# BlinkBoard_micro_v1.net
KiCad netlist of a schematic drawn in Altium Designer
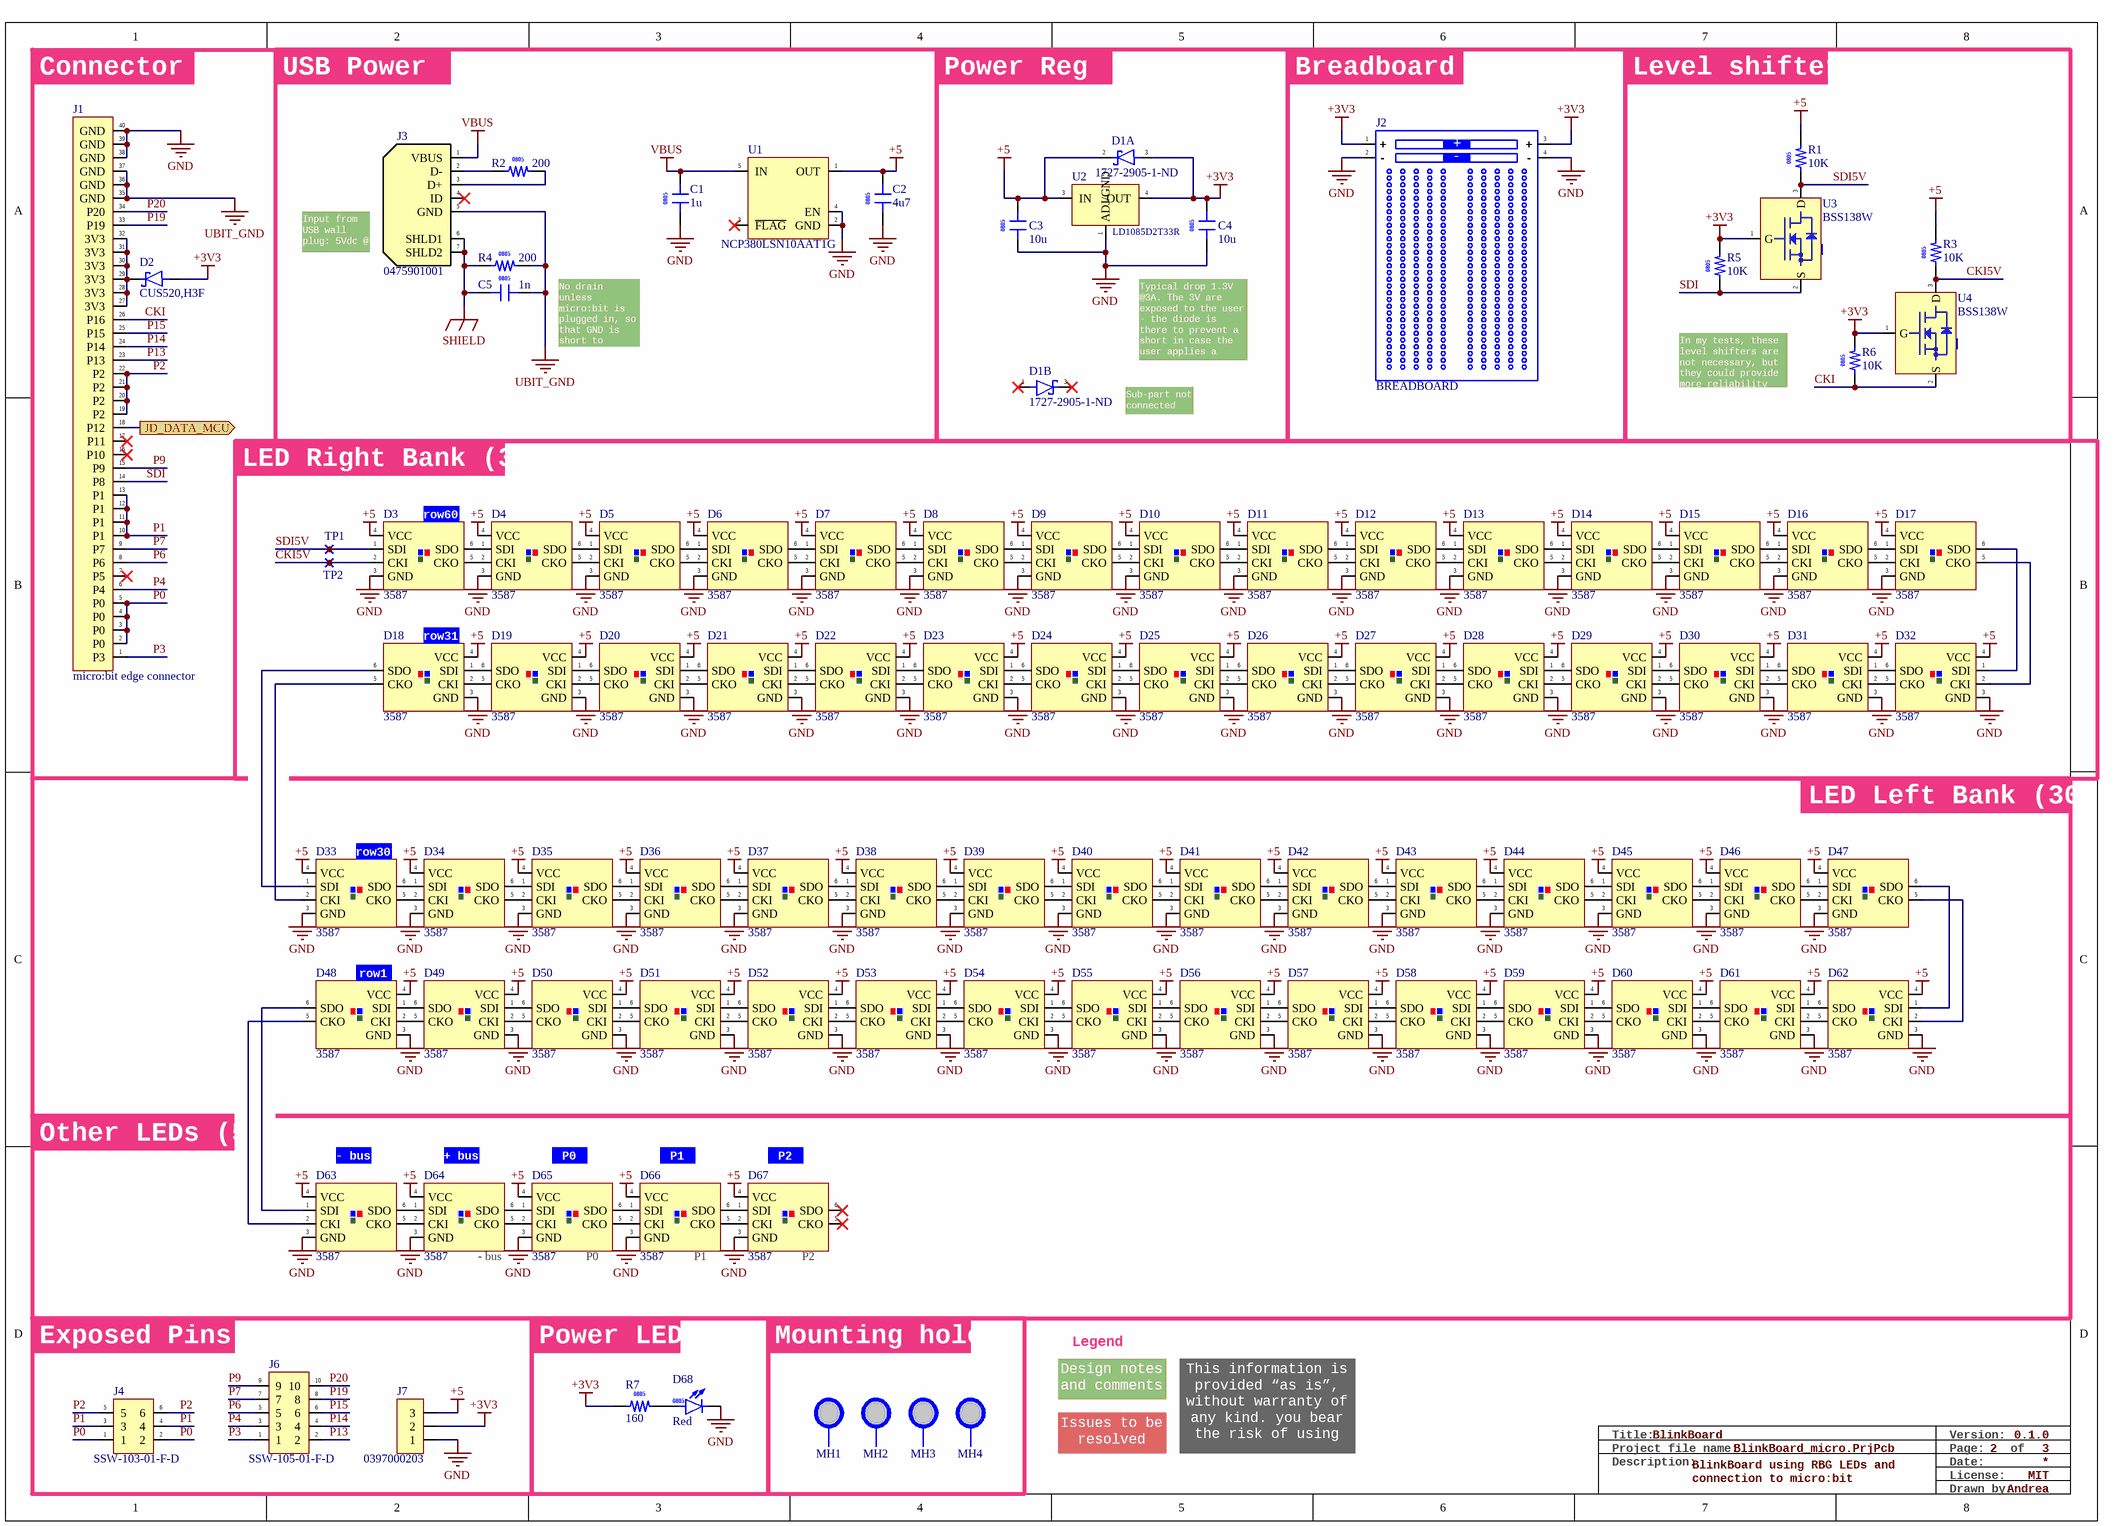
[diagram p0: BlinkBoard_micro_v1.SchDoc]

(export (version "E")
  (design (tool "Eeschema 10.0.6"))
  (components
    (comp (ref "C1")
      (value "1u")
      (footprint "C0805")
      (description "Surface Mount Ceramic Multilayer Capacitor 1uF -20% to 80% Y5V 25V 0805 Paper T/R")
      (fields
        (field (name "MANUFACTURER") "Yageo")
        (field (name "MANUFACTURER PART NUMBER") "CC0805ZRY5V8BB105")
      )
      (libsource (lib "Passives") (part "C0805_1u"))
    )
    (comp (ref "C2")
      (value "4u7")
      (footprint "C0805")
      (description "Multilayer Ceramic Capacitors MLCC - SMD/SMT 4.7uF 6.3V X5R 10%")
      (fields
        (field (name "MANUFACTURER") "Yageo")
        (field (name "MANUFACTURER PART NUMBER") "CC0805KRX5R5BB475")
      )
      (libsource (lib "Passives") (part "C0805_4u7"))
    )
    (comp (ref "C3")
      (value "10u")
      (footprint "C0805")
      (description "Cap Ceramic 10uF 10Vdc X5R 10% SMD 0805 85°C Paper T/R")
      (fields
        (field (name "MANUFACTURER") "Yageo")
        (field (name "MANUFACTURER PART NUMBER") "CC0805KPX5R6BB106")
      )
      (libsource (lib "Passives") (part "C0805_10u"))
    )
    (comp (ref "C4")
      (value "10u")
      (footprint "C0805")
      (description "Cap Ceramic 10uF 10Vdc X5R 10% SMD 0805 85°C Paper T/R")
      (fields
        (field (name "MANUFACTURER") "Yageo")
        (field (name "MANUFACTURER PART NUMBER") "CC0805KPX5R6BB106")
      )
      (libsource (lib "Passives") (part "C0805_10u"))
    )
    (comp (ref "C5")
      (value "1n")
      (footprint "C0805")
      (description "Surface Mount Ceramic Multilayer Capacitor 0.001uF 10% X7R 50V 0805 Paper T/R")
      (fields
        (field (name "MANUFACTURER") "Yageo")
        (field (name "MANUFACTURER PART NUMBER") "CC0805KRX7R9BB102")
      )
      (libsource (lib "Passives") (part "C0805_1n"))
    )
    (comp (ref "D1")
      (value "1727-2905-1-ND")
      (footprint "SOT323")
      (description "Rectifier Diode Schottky 0.2A 5ns Automotive 3-Pin SC-70 T/R")
      (fields
        (field (name "MANUFACTURER") "Nexperia")
        (field (name "MANUFACTURER PART NUMBER") "BAT54SW,115")
      )
      (libsource (lib "Diodes") (part "BAT54SW"))
    )
    (comp (ref "D2")
      (value "CUS520,H3F")
      (footprint "FP-USC-MFG")
      (description "Diode Small Signal Schottky Si 0.2A 2-Pin USC T/R")
      (fields (field (name "MANUFACTURER") "Toshiba"))
      (libsource (lib "Diodes") (part "SCHOTTKY_0.2A"))
    )
    (comp (ref "D3")
      (value "3587")
      (footprint "APA102-2020")
      (description "DotStar Micro LEDs (APA102–2020)- Smart SMD RGB LED - 100 pack")
      (fields (field (name "MANUFACTURER") "Adafruit Industries"))
      (libsource (lib "Diodes") (part "DOT_STAR_LED"))
    )
    (comp (ref "D4")
      (value "3587")
      (footprint "APA102-2020")
      (description "DotStar Micro LEDs (APA102–2020)- Smart SMD RGB LED - 100 pack")
      (fields (field (name "MANUFACTURER") "Adafruit Industries"))
      (libsource (lib "Diodes") (part "DOT_STAR_LED"))
    )
    (comp (ref "D5")
      (value "3587")
      (footprint "APA102-2020")
      (description "DotStar Micro LEDs (APA102–2020)- Smart SMD RGB LED - 100 pack")
      (fields (field (name "MANUFACTURER") "Adafruit Industries"))
      (libsource (lib "Diodes") (part "DOT_STAR_LED"))
    )
    (comp (ref "D6")
      (value "3587")
      (footprint "APA102-2020")
      (description "DotStar Micro LEDs (APA102–2020)- Smart SMD RGB LED - 100 pack")
      (fields (field (name "MANUFACTURER") "Adafruit Industries"))
      (libsource (lib "Diodes") (part "DOT_STAR_LED"))
    )
    (comp (ref "D7")
      (value "3587")
      (footprint "APA102-2020")
      (description "DotStar Micro LEDs (APA102–2020)- Smart SMD RGB LED - 100 pack")
      (fields (field (name "MANUFACTURER") "Adafruit Industries"))
      (libsource (lib "Diodes") (part "DOT_STAR_LED"))
    )
    (comp (ref "D8")
      (value "3587")
      (footprint "APA102-2020")
      (description "DotStar Micro LEDs (APA102–2020)- Smart SMD RGB LED - 100 pack")
      (fields (field (name "MANUFACTURER") "Adafruit Industries"))
      (libsource (lib "Diodes") (part "DOT_STAR_LED"))
    )
    (comp (ref "D9")
      (value "3587")
      (footprint "APA102-2020")
      (description "DotStar Micro LEDs (APA102–2020)- Smart SMD RGB LED - 100 pack")
      (fields (field (name "MANUFACTURER") "Adafruit Industries"))
      (libsource (lib "Diodes") (part "DOT_STAR_LED"))
    )
    (comp (ref "D10")
      (value "3587")
      (footprint "APA102-2020")
      (description "DotStar Micro LEDs (APA102–2020)- Smart SMD RGB LED - 100 pack")
      (fields (field (name "MANUFACTURER") "Adafruit Industries"))
      (libsource (lib "Diodes") (part "DOT_STAR_LED"))
    )
    (comp (ref "D11")
      (value "3587")
      (footprint "APA102-2020")
      (description "DotStar Micro LEDs (APA102–2020)- Smart SMD RGB LED - 100 pack")
      (fields (field (name "MANUFACTURER") "Adafruit Industries"))
      (libsource (lib "Diodes") (part "DOT_STAR_LED"))
    )
    (comp (ref "D12")
      (value "3587")
      (footprint "APA102-2020")
      (description "DotStar Micro LEDs (APA102–2020)- Smart SMD RGB LED - 100 pack")
      (fields (field (name "MANUFACTURER") "Adafruit Industries"))
      (libsource (lib "Diodes") (part "DOT_STAR_LED"))
    )
    (comp (ref "D13")
      (value "3587")
      (footprint "APA102-2020")
      (description "DotStar Micro LEDs (APA102–2020)- Smart SMD RGB LED - 100 pack")
      (fields (field (name "MANUFACTURER") "Adafruit Industries"))
      (libsource (lib "Diodes") (part "DOT_STAR_LED"))
    )
    (comp (ref "D14")
      (value "3587")
      (footprint "APA102-2020")
      (description "DotStar Micro LEDs (APA102–2020)- Smart SMD RGB LED - 100 pack")
      (fields (field (name "MANUFACTURER") "Adafruit Industries"))
      (libsource (lib "Diodes") (part "DOT_STAR_LED"))
    )
    (comp (ref "D15")
      (value "3587")
      (footprint "APA102-2020")
      (description "DotStar Micro LEDs (APA102–2020)- Smart SMD RGB LED - 100 pack")
      (fields (field (name "MANUFACTURER") "Adafruit Industries"))
      (libsource (lib "Diodes") (part "DOT_STAR_LED"))
    )
    (comp (ref "D16")
      (value "3587")
      (footprint "APA102-2020")
      (description "DotStar Micro LEDs (APA102–2020)- Smart SMD RGB LED - 100 pack")
      (fields (field (name "MANUFACTURER") "Adafruit Industries"))
      (libsource (lib "Diodes") (part "DOT_STAR_LED"))
    )
    (comp (ref "D17")
      (value "3587")
      (footprint "APA102-2020")
      (description "DotStar Micro LEDs (APA102–2020)- Smart SMD RGB LED - 100 pack")
      (fields (field (name "MANUFACTURER") "Adafruit Industries"))
      (libsource (lib "Diodes") (part "DOT_STAR_LED"))
    )
    (comp (ref "D18")
      (value "3587")
      (footprint "APA102-2020")
      (description "DotStar Micro LEDs (APA102–2020)- Smart SMD RGB LED - 100 pack")
      (fields (field (name "MANUFACTURER") "Adafruit Industries"))
      (libsource (lib "") (part "DOT_STAR_LED_1"))
    )
    (comp (ref "D19")
      (value "3587")
      (footprint "APA102-2020")
      (description "DotStar Micro LEDs (APA102–2020)- Smart SMD RGB LED - 100 pack")
      (fields (field (name "MANUFACTURER") "Adafruit Industries"))
      (libsource (lib "") (part "DOT_STAR_LED_1"))
    )
    (comp (ref "D20")
      (value "3587")
      (footprint "APA102-2020")
      (description "DotStar Micro LEDs (APA102–2020)- Smart SMD RGB LED - 100 pack")
      (fields (field (name "MANUFACTURER") "Adafruit Industries"))
      (libsource (lib "") (part "DOT_STAR_LED_1"))
    )
    (comp (ref "D21")
      (value "3587")
      (footprint "APA102-2020")
      (description "DotStar Micro LEDs (APA102–2020)- Smart SMD RGB LED - 100 pack")
      (fields (field (name "MANUFACTURER") "Adafruit Industries"))
      (libsource (lib "") (part "DOT_STAR_LED_1"))
    )
    (comp (ref "D22")
      (value "3587")
      (footprint "APA102-2020")
      (description "DotStar Micro LEDs (APA102–2020)- Smart SMD RGB LED - 100 pack")
      (fields (field (name "MANUFACTURER") "Adafruit Industries"))
      (libsource (lib "") (part "DOT_STAR_LED_1"))
    )
    (comp (ref "D23")
      (value "3587")
      (footprint "APA102-2020")
      (description "DotStar Micro LEDs (APA102–2020)- Smart SMD RGB LED - 100 pack")
      (fields (field (name "MANUFACTURER") "Adafruit Industries"))
      (libsource (lib "") (part "DOT_STAR_LED_1"))
    )
    (comp (ref "D24")
      (value "3587")
      (footprint "APA102-2020")
      (description "DotStar Micro LEDs (APA102–2020)- Smart SMD RGB LED - 100 pack")
      (fields (field (name "MANUFACTURER") "Adafruit Industries"))
      (libsource (lib "") (part "DOT_STAR_LED_1"))
    )
    (comp (ref "D25")
      (value "3587")
      (footprint "APA102-2020")
      (description "DotStar Micro LEDs (APA102–2020)- Smart SMD RGB LED - 100 pack")
      (fields (field (name "MANUFACTURER") "Adafruit Industries"))
      (libsource (lib "") (part "DOT_STAR_LED_1"))
    )
    (comp (ref "D26")
      (value "3587")
      (footprint "APA102-2020")
      (description "DotStar Micro LEDs (APA102–2020)- Smart SMD RGB LED - 100 pack")
      (fields (field (name "MANUFACTURER") "Adafruit Industries"))
      (libsource (lib "") (part "DOT_STAR_LED_1"))
    )
    (comp (ref "D27")
      (value "3587")
      (footprint "APA102-2020")
      (description "DotStar Micro LEDs (APA102–2020)- Smart SMD RGB LED - 100 pack")
      (fields (field (name "MANUFACTURER") "Adafruit Industries"))
      (libsource (lib "") (part "DOT_STAR_LED_1"))
    )
    (comp (ref "D28")
      (value "3587")
      (footprint "APA102-2020")
      (description "DotStar Micro LEDs (APA102–2020)- Smart SMD RGB LED - 100 pack")
      (fields (field (name "MANUFACTURER") "Adafruit Industries"))
      (libsource (lib "") (part "DOT_STAR_LED_1"))
    )
    (comp (ref "D29")
      (value "3587")
      (footprint "APA102-2020")
      (description "DotStar Micro LEDs (APA102–2020)- Smart SMD RGB LED - 100 pack")
      (fields (field (name "MANUFACTURER") "Adafruit Industries"))
      (libsource (lib "") (part "DOT_STAR_LED_1"))
    )
    (comp (ref "D30")
      (value "3587")
      (footprint "APA102-2020")
      (description "DotStar Micro LEDs (APA102–2020)- Smart SMD RGB LED - 100 pack")
      (fields (field (name "MANUFACTURER") "Adafruit Industries"))
      (libsource (lib "") (part "DOT_STAR_LED_1"))
    )
    (comp (ref "D31")
      (value "3587")
      (footprint "APA102-2020")
      (description "DotStar Micro LEDs (APA102–2020)- Smart SMD RGB LED - 100 pack")
      (fields (field (name "MANUFACTURER") "Adafruit Industries"))
      (libsource (lib "") (part "DOT_STAR_LED_1"))
    )
    (comp (ref "D32")
      (value "3587")
      (footprint "APA102-2020")
      (description "DotStar Micro LEDs (APA102–2020)- Smart SMD RGB LED - 100 pack")
      (fields (field (name "MANUFACTURER") "Adafruit Industries"))
      (libsource (lib "") (part "DOT_STAR_LED_1"))
    )
    (comp (ref "D33")
      (value "3587")
      (footprint "APA102-2020")
      (description "DotStar Micro LEDs (APA102–2020)- Smart SMD RGB LED - 100 pack")
      (fields (field (name "MANUFACTURER") "Adafruit Industries"))
      (libsource (lib "Diodes") (part "DOT_STAR_LED"))
    )
    (comp (ref "D34")
      (value "3587")
      (footprint "APA102-2020")
      (description "DotStar Micro LEDs (APA102–2020)- Smart SMD RGB LED - 100 pack")
      (fields (field (name "MANUFACTURER") "Adafruit Industries"))
      (libsource (lib "Diodes") (part "DOT_STAR_LED"))
    )
    (comp (ref "D35")
      (value "3587")
      (footprint "APA102-2020")
      (description "DotStar Micro LEDs (APA102–2020)- Smart SMD RGB LED - 100 pack")
      (fields (field (name "MANUFACTURER") "Adafruit Industries"))
      (libsource (lib "Diodes") (part "DOT_STAR_LED"))
    )
    (comp (ref "D36")
      (value "3587")
      (footprint "APA102-2020")
      (description "DotStar Micro LEDs (APA102–2020)- Smart SMD RGB LED - 100 pack")
      (fields (field (name "MANUFACTURER") "Adafruit Industries"))
      (libsource (lib "Diodes") (part "DOT_STAR_LED"))
    )
    (comp (ref "D37")
      (value "3587")
      (footprint "APA102-2020")
      (description "DotStar Micro LEDs (APA102–2020)- Smart SMD RGB LED - 100 pack")
      (fields (field (name "MANUFACTURER") "Adafruit Industries"))
      (libsource (lib "Diodes") (part "DOT_STAR_LED"))
    )
    (comp (ref "D38")
      (value "3587")
      (footprint "APA102-2020")
      (description "DotStar Micro LEDs (APA102–2020)- Smart SMD RGB LED - 100 pack")
      (fields (field (name "MANUFACTURER") "Adafruit Industries"))
      (libsource (lib "Diodes") (part "DOT_STAR_LED"))
    )
    (comp (ref "D39")
      (value "3587")
      (footprint "APA102-2020")
      (description "DotStar Micro LEDs (APA102–2020)- Smart SMD RGB LED - 100 pack")
      (fields (field (name "MANUFACTURER") "Adafruit Industries"))
      (libsource (lib "Diodes") (part "DOT_STAR_LED"))
    )
    (comp (ref "D40")
      (value "3587")
      (footprint "APA102-2020")
      (description "DotStar Micro LEDs (APA102–2020)- Smart SMD RGB LED - 100 pack")
      (fields (field (name "MANUFACTURER") "Adafruit Industries"))
      (libsource (lib "Diodes") (part "DOT_STAR_LED"))
    )
    (comp (ref "D41")
      (value "3587")
      (footprint "APA102-2020")
      (description "DotStar Micro LEDs (APA102–2020)- Smart SMD RGB LED - 100 pack")
      (fields (field (name "MANUFACTURER") "Adafruit Industries"))
      (libsource (lib "Diodes") (part "DOT_STAR_LED"))
    )
    (comp (ref "D42")
      (value "3587")
      (footprint "APA102-2020")
      (description "DotStar Micro LEDs (APA102–2020)- Smart SMD RGB LED - 100 pack")
      (fields (field (name "MANUFACTURER") "Adafruit Industries"))
      (libsource (lib "Diodes") (part "DOT_STAR_LED"))
    )
    (comp (ref "D43")
      (value "3587")
      (footprint "APA102-2020")
      (description "DotStar Micro LEDs (APA102–2020)- Smart SMD RGB LED - 100 pack")
      (fields (field (name "MANUFACTURER") "Adafruit Industries"))
      (libsource (lib "Diodes") (part "DOT_STAR_LED"))
    )
    (comp (ref "D44")
      (value "3587")
      (footprint "APA102-2020")
      (description "DotStar Micro LEDs (APA102–2020)- Smart SMD RGB LED - 100 pack")
      (fields (field (name "MANUFACTURER") "Adafruit Industries"))
      (libsource (lib "Diodes") (part "DOT_STAR_LED"))
    )
    (comp (ref "D45")
      (value "3587")
      (footprint "APA102-2020")
      (description "DotStar Micro LEDs (APA102–2020)- Smart SMD RGB LED - 100 pack")
      (fields (field (name "MANUFACTURER") "Adafruit Industries"))
      (libsource (lib "Diodes") (part "DOT_STAR_LED"))
    )
    (comp (ref "D46")
      (value "3587")
      (footprint "APA102-2020")
      (description "DotStar Micro LEDs (APA102–2020)- Smart SMD RGB LED - 100 pack")
      (fields (field (name "MANUFACTURER") "Adafruit Industries"))
      (libsource (lib "Diodes") (part "DOT_STAR_LED"))
    )
    (comp (ref "D47")
      (value "3587")
      (footprint "APA102-2020")
      (description "DotStar Micro LEDs (APA102–2020)- Smart SMD RGB LED - 100 pack")
      (fields (field (name "MANUFACTURER") "Adafruit Industries"))
      (libsource (lib "Diodes") (part "DOT_STAR_LED"))
    )
    (comp (ref "D48")
      (value "3587")
      (footprint "APA102-2020")
      (description "DotStar Micro LEDs (APA102–2020)- Smart SMD RGB LED - 100 pack")
      (fields (field (name "MANUFACTURER") "Adafruit Industries"))
      (libsource (lib "") (part "DOT_STAR_LED_1"))
    )
    (comp (ref "D49")
      (value "3587")
      (footprint "APA102-2020")
      (description "DotStar Micro LEDs (APA102–2020)- Smart SMD RGB LED - 100 pack")
      (fields (field (name "MANUFACTURER") "Adafruit Industries"))
      (libsource (lib "") (part "DOT_STAR_LED_1"))
    )
    (comp (ref "D50")
      (value "3587")
      (footprint "APA102-2020")
      (description "DotStar Micro LEDs (APA102–2020)- Smart SMD RGB LED - 100 pack")
      (fields (field (name "MANUFACTURER") "Adafruit Industries"))
      (libsource (lib "") (part "DOT_STAR_LED_1"))
    )
    (comp (ref "D51")
      (value "3587")
      (footprint "APA102-2020")
      (description "DotStar Micro LEDs (APA102–2020)- Smart SMD RGB LED - 100 pack")
      (fields (field (name "MANUFACTURER") "Adafruit Industries"))
      (libsource (lib "") (part "DOT_STAR_LED_1"))
    )
    (comp (ref "D52")
      (value "3587")
      (footprint "APA102-2020")
      (description "DotStar Micro LEDs (APA102–2020)- Smart SMD RGB LED - 100 pack")
      (fields (field (name "MANUFACTURER") "Adafruit Industries"))
      (libsource (lib "") (part "DOT_STAR_LED_1"))
    )
    (comp (ref "D53")
      (value "3587")
      (footprint "APA102-2020")
      (description "DotStar Micro LEDs (APA102–2020)- Smart SMD RGB LED - 100 pack")
      (fields (field (name "MANUFACTURER") "Adafruit Industries"))
      (libsource (lib "") (part "DOT_STAR_LED_1"))
    )
    (comp (ref "D54")
      (value "3587")
      (footprint "APA102-2020")
      (description "DotStar Micro LEDs (APA102–2020)- Smart SMD RGB LED - 100 pack")
      (fields (field (name "MANUFACTURER") "Adafruit Industries"))
      (libsource (lib "") (part "DOT_STAR_LED_1"))
    )
    (comp (ref "D55")
      (value "3587")
      (footprint "APA102-2020")
      (description "DotStar Micro LEDs (APA102–2020)- Smart SMD RGB LED - 100 pack")
      (fields (field (name "MANUFACTURER") "Adafruit Industries"))
      (libsource (lib "") (part "DOT_STAR_LED_1"))
    )
    (comp (ref "D56")
      (value "3587")
      (footprint "APA102-2020")
      (description "DotStar Micro LEDs (APA102–2020)- Smart SMD RGB LED - 100 pack")
      (fields (field (name "MANUFACTURER") "Adafruit Industries"))
      (libsource (lib "") (part "DOT_STAR_LED_1"))
    )
    (comp (ref "D57")
      (value "3587")
      (footprint "APA102-2020")
      (description "DotStar Micro LEDs (APA102–2020)- Smart SMD RGB LED - 100 pack")
      (fields (field (name "MANUFACTURER") "Adafruit Industries"))
      (libsource (lib "") (part "DOT_STAR_LED_1"))
    )
    (comp (ref "D58")
      (value "3587")
      (footprint "APA102-2020")
      (description "DotStar Micro LEDs (APA102–2020)- Smart SMD RGB LED - 100 pack")
      (fields (field (name "MANUFACTURER") "Adafruit Industries"))
      (libsource (lib "") (part "DOT_STAR_LED_1"))
    )
    (comp (ref "D59")
      (value "3587")
      (footprint "APA102-2020")
      (description "DotStar Micro LEDs (APA102–2020)- Smart SMD RGB LED - 100 pack")
      (fields (field (name "MANUFACTURER") "Adafruit Industries"))
      (libsource (lib "") (part "DOT_STAR_LED_1"))
    )
    (comp (ref "D60")
      (value "3587")
      (footprint "APA102-2020")
      (description "DotStar Micro LEDs (APA102–2020)- Smart SMD RGB LED - 100 pack")
      (fields (field (name "MANUFACTURER") "Adafruit Industries"))
      (libsource (lib "") (part "DOT_STAR_LED_1"))
    )
    (comp (ref "D61")
      (value "3587")
      (footprint "APA102-2020")
      (description "DotStar Micro LEDs (APA102–2020)- Smart SMD RGB LED - 100 pack")
      (fields (field (name "MANUFACTURER") "Adafruit Industries"))
      (libsource (lib "") (part "DOT_STAR_LED_1"))
    )
    (comp (ref "D62")
      (value "3587")
      (footprint "APA102-2020")
      (description "DotStar Micro LEDs (APA102–2020)- Smart SMD RGB LED - 100 pack")
      (fields (field (name "MANUFACTURER") "Adafruit Industries"))
      (libsource (lib "") (part "DOT_STAR_LED_1"))
    )
    (comp (ref "D63")
      (value "3587")
      (footprint "APA102-2020")
      (description "DotStar Micro LEDs (APA102–2020)- Smart SMD RGB LED - 100 pack")
      (fields (field (name "MANUFACTURER") "Adafruit Industries"))
      (libsource (lib "Diodes") (part "DOT_STAR_LED"))
    )
    (comp (ref "D64")
      (value "3587")
      (footprint "APA102-2020")
      (description "DotStar Micro LEDs (APA102–2020)- Smart SMD RGB LED - 100 pack")
      (fields (field (name "MANUFACTURER") "Adafruit Industries"))
      (libsource (lib "Diodes") (part "DOT_STAR_LED"))
    )
    (comp (ref "D65")
      (value "3587")
      (footprint "APA102-2020")
      (description "DotStar Micro LEDs (APA102–2020)- Smart SMD RGB LED - 100 pack")
      (fields (field (name "MANUFACTURER") "Adafruit Industries"))
      (libsource (lib "Diodes") (part "DOT_STAR_LED"))
    )
    (comp (ref "D66")
      (value "3587")
      (footprint "APA102-2020")
      (description "DotStar Micro LEDs (APA102–2020)- Smart SMD RGB LED - 100 pack")
      (fields (field (name "MANUFACTURER") "Adafruit Industries"))
      (libsource (lib "Diodes") (part "DOT_STAR_LED"))
    )
    (comp (ref "D67")
      (value "3587")
      (footprint "APA102-2020")
      (description "DotStar Micro LEDs (APA102–2020)- Smart SMD RGB LED - 100 pack")
      (fields (field (name "MANUFACTURER") "Adafruit Industries"))
      (libsource (lib "Diodes") (part "DOT_STAR_LED"))
    )
    (comp (ref "D68")
      (value "Red")
      (footprint "LED0805")
      (description "SMD LED red 2.4 V 0805, 150080RS75000, Würth Elektronik")
      (fields
        (field (name "MANUFACTURER") "Wurth Electronics")
        (field (name "MANUFACTURER PART NUMBER") "150080RS75000")
      )
      (libsource (lib "Diodes") (part "LED0805"))
    )
    (comp (ref "J1")
      (value "micro:bit edge connector")
      (footprint "EDGE_CONNECTOR_40")
      (description "3887 - SMT Right-Angle Connector for micro:bit")
      (fields
        (field (name "MANUFACTURER") "Adafruit Industries")
        (field (name "MANUFACTURER PART NUMBER") "3887")
      )
      (libsource (lib "Mechanical") (part "EDGE_CONNECTOR_40"))
    )
    (comp (ref "J2")
      (value "BREADBOARD")
      (footprint "BREADBOARD")
      (description "Breadboard with 2 columns of 30 rows + VCC and GND rails")
      (libsource (lib "Mechanical") (part "BREADBOARD_60"))
    )
    (comp (ref "J3")
      (value "0475901001")
      (footprint "USB_MICRO")
      (description "USB - micro AB  Receptacle Connector 5 Position Surface Mount, Right Angle, Horizontal")
      (fields (field (name "MANUFACTURER") "Molex"))
      (libsource (lib "Mechanical") (part "USB_MICRO"))
    )
    (comp (ref "J4")
      (value "SSW-103-01-F-D")
      (footprint "HDR_6_2.54")
      (description "SAMTEC - SSW-103-01-F-D - CONNECTOR, RECEPTACLE, 6 CONTACTS, 2 ROWS, 2.54 MM")
      (fields (field (name "MANUFACTURER") "Samtec"))
      (libsource (lib "Mechanical") (part "HDR_6_2.54"))
    )
    (comp (ref "J6")
      (value "SSW-105-01-F-D")
      (footprint "HDR_10_2.54")
      (description "Conn Socket Strip SKT 10 POS 2.54mm Solder ST Thru-Hole")
      (fields (field (name "MANUFACTURER") "Samtec"))
      (libsource (lib "Mechanical") (part "HDR_10_2.54"))
    )
    (comp (ref "J7")
      (value "0397000203")
      (footprint "TERM_BLOCK_3POS")
      (description "SPRING TERMINAL BLOCK 3CVERT GRE")
      (fields (field (name "MANUFACTURER") "Molex") (field (name "VOLTAGE") "150V"))
      (libsource (lib "Mechanical") (part "TERM_BLOCK_3POS"))
    )
    (comp (ref "MH1")
      (value "MH 3.2mm NP")
      (footprint "MH3.2MM")
      (description "Mounting hole 3.2mm non plated")
      (libsource (lib "Mechanical") (part "MHNP"))
    )
    (comp (ref "MH2")
      (value "MH 3.2mm NP")
      (footprint "MH3.2MM")
      (description "Mounting hole 3.2mm non plated")
      (libsource (lib "Mechanical") (part "MHNP"))
    )
    (comp (ref "MH3")
      (value "MH 3.2mm NP")
      (footprint "MH3.2MM")
      (description "Mounting hole 3.2mm non plated")
      (libsource (lib "Mechanical") (part "MHNP"))
    )
    (comp (ref "MH4")
      (value "MH 3.2mm NP")
      (footprint "MH3.2MM")
      (description "Mounting hole 3.2mm non plated")
      (libsource (lib "Mechanical") (part "MHNP"))
    )
    (comp (ref "R1")
      (value "10K")
      (footprint "R0805")
      (description "Res Thick Film 0805 10K Ohm 5% 1/8W ±100ppm/°C Molded SMD Paper T/R")
      (fields
        (field (name "MANUFACTURER") "Yageo")
        (field (name "MANUFACTURER PART NUMBER") "RC0805JR-0710KL")
      )
      (libsource (lib "Passives") (part "R0805_10K"))
    )
    (comp (ref "R2")
      (value "200")
      (footprint "R0805")
      (description "RES SMD 200 OHM 0.5% 1/8W 0805")
      (fields
        (field (name "MANUFACTURER") "Yageo")
        (field (name "MANUFACTURER PART NUMBER") "RT0805DRE07200RL")
      )
      (libsource (lib "Passives") (part "R0805_200"))
    )
    (comp (ref "R3")
      (value "10K")
      (footprint "R0805")
      (description "Res Thick Film 0805 10K Ohm 5% 1/8W ±100ppm/°C Molded SMD Paper T/R")
      (fields
        (field (name "MANUFACTURER") "Yageo")
        (field (name "MANUFACTURER PART NUMBER") "RC0805JR-0710KL")
      )
      (libsource (lib "Passives") (part "R0805_10K"))
    )
    (comp (ref "R4")
      (value "200")
      (footprint "R0805")
      (description "RES SMD 200 OHM 0.5% 1/8W 0805")
      (fields
        (field (name "MANUFACTURER") "Yageo")
        (field (name "MANUFACTURER PART NUMBER") "RT0805DRE07200RL")
      )
      (libsource (lib "Passives") (part "R0805_200"))
    )
    (comp (ref "R5")
      (value "10K")
      (footprint "R0805")
      (description "Res Thick Film 0805 10K Ohm 5% 1/8W ±100ppm/°C Molded SMD Paper T/R")
      (fields
        (field (name "MANUFACTURER") "Yageo")
        (field (name "MANUFACTURER PART NUMBER") "RC0805JR-0710KL")
      )
      (libsource (lib "Passives") (part "R0805_10K"))
    )
    (comp (ref "R6")
      (value "10K")
      (footprint "R0805")
      (description "Res Thick Film 0805 10K Ohm 5% 1/8W ±100ppm/°C Molded SMD Paper T/R")
      (fields
        (field (name "MANUFACTURER") "Yageo")
        (field (name "MANUFACTURER PART NUMBER") "RC0805JR-0710KL")
      )
      (libsource (lib "Passives") (part "R0805_10K"))
    )
    (comp (ref "R7")
      (value "160")
      (footprint "R0805")
      (description "RES SMD 160 OHM 5% 1/8W 0805")
      (fields
        (field (name "MANUFACTURER") "Yageo")
        (field (name "MANUFACTURER PART NUMBER") "RC0805JR-07160RL")
      )
      (libsource (lib "Passives") (part "R0805_160"))
    )
    (comp (ref "TP1")
      (value "TEST")
      (footprint "TEST POINT")
      (description "Test point")
      (libsource (lib "Mechanical") (part "TEST"))
    )
    (comp (ref "TP2")
      (value "TEST")
      (footprint "TEST POINT")
      (description "Test point")
      (libsource (lib "Mechanical") (part "TEST"))
    )
    (comp (ref "U1")
      (value "NCP380LSN10AAT1G")
      (footprint "TSOP-5")
      (description "REEL / OVER CURRENT PROTECTION")
      (fields (field (name "MANUFACTURER") "ON Semiconductor"))
      (libsource (lib "IC") (part "NCP380"))
    )
    (comp (ref "U2")
      (value "LD1085D2T33R")
      (footprint "D2PAK")
      (description "Fixed LDO Voltage Regulator, 6.3V to 30V, 1.3V Dropout, 3.3Vout, 3Aout, TO-263-3")
      (fields (field (name "MANUFACTURER") "STMicroelectronics"))
      (libsource (lib "IC") (part "LD1085D2T33R"))
    )
    (comp (ref "U3")
      (value "BSS138W")
      (footprint "SOT323")
      (description "MOSFET 50V N-CH Logic Level")
      (fields (field (name "MANUFACTURER") "Fairchild Semiconductor"))
      (libsource (lib "IC") (part "BSS138W"))
    )
    (comp (ref "U4")
      (value "BSS138W")
      (footprint "SOT323")
      (description "MOSFET 50V N-CH Logic Level")
      (fields (field (name "MANUFACTURER") "Fairchild Semiconductor"))
      (libsource (lib "IC") (part "BSS138W"))
    )
  )
  (nets
    (net (code "1") (name "+3V3") (class "Default")
      (node (ref "C4") (pin "2") (pinfunction "2_2") (pintype "passive"))
      (node (ref "D1") (pin "3") (pinfunction "3_3") (pintype "passive"))
      (node (ref "D2") (pin "2") (pinfunction "A_2") (pintype "passive"))
      (node (ref "J2") (pin "1") (pinfunction "+_1") (pintype "passive"))
      (node (ref "J2") (pin "3") (pinfunction "+_3") (pintype "passive"))
      (node (ref "J7") (pin "2") (pinfunction "2_2") (pintype "passive"))
      (node (ref "R5") (pin "2") (pinfunction "2_2") (pintype "passive"))
      (node (ref "R6") (pin "2") (pinfunction "2_2") (pintype "passive"))
      (node (ref "R7") (pin "1") (pinfunction "1_1") (pintype "passive"))
      (node (ref "U2") (pin "4") (pinfunction "OUT_4") (pintype "passive"))
      (node (ref "U3") (pin "1") (pinfunction "G_1") (pintype "passive"))
      (node (ref "U4") (pin "1") (pinfunction "G_1") (pintype "passive"))
    )
    (net (code "2") (name "+5") (class "Default")
      (node (ref "C2") (pin "2") (pinfunction "2_2") (pintype "passive"))
      (node (ref "C3") (pin "2") (pinfunction "2_2") (pintype "passive"))
      (node (ref "D1") (pin "2") (pinfunction "2_2") (pintype "passive"))
      (node (ref "D10") (pin "4") (pinfunction "VCC_4") (pintype "passive"))
      (node (ref "D11") (pin "4") (pinfunction "VCC_4") (pintype "passive"))
      (node (ref "D12") (pin "4") (pinfunction "VCC_4") (pintype "passive"))
      (node (ref "D13") (pin "4") (pinfunction "VCC_4") (pintype "passive"))
      (node (ref "D14") (pin "4") (pinfunction "VCC_4") (pintype "passive"))
      (node (ref "D15") (pin "4") (pinfunction "VCC_4") (pintype "passive"))
      (node (ref "D16") (pin "4") (pinfunction "VCC_4") (pintype "passive"))
      (node (ref "D17") (pin "4") (pinfunction "VCC_4") (pintype "passive"))
      (node (ref "D18") (pin "4") (pinfunction "VCC_4") (pintype "passive"))
      (node (ref "D19") (pin "4") (pinfunction "VCC_4") (pintype "passive"))
      (node (ref "D20") (pin "4") (pinfunction "VCC_4") (pintype "passive"))
      (node (ref "D21") (pin "4") (pinfunction "VCC_4") (pintype "passive"))
      (node (ref "D22") (pin "4") (pinfunction "VCC_4") (pintype "passive"))
      (node (ref "D23") (pin "4") (pinfunction "VCC_4") (pintype "passive"))
      (node (ref "D24") (pin "4") (pinfunction "VCC_4") (pintype "passive"))
      (node (ref "D25") (pin "4") (pinfunction "VCC_4") (pintype "passive"))
      (node (ref "D26") (pin "4") (pinfunction "VCC_4") (pintype "passive"))
      (node (ref "D27") (pin "4") (pinfunction "VCC_4") (pintype "passive"))
      (node (ref "D28") (pin "4") (pinfunction "VCC_4") (pintype "passive"))
      (node (ref "D29") (pin "4") (pinfunction "VCC_4") (pintype "passive"))
      (node (ref "D3") (pin "4") (pinfunction "VCC_4") (pintype "passive"))
      (node (ref "D30") (pin "4") (pinfunction "VCC_4") (pintype "passive"))
      (node (ref "D31") (pin "4") (pinfunction "VCC_4") (pintype "passive"))
      (node (ref "D32") (pin "4") (pinfunction "VCC_4") (pintype "passive"))
      (node (ref "D33") (pin "4") (pinfunction "VCC_4") (pintype "passive"))
      (node (ref "D34") (pin "4") (pinfunction "VCC_4") (pintype "passive"))
      (node (ref "D35") (pin "4") (pinfunction "VCC_4") (pintype "passive"))
      (node (ref "D36") (pin "4") (pinfunction "VCC_4") (pintype "passive"))
      (node (ref "D37") (pin "4") (pinfunction "VCC_4") (pintype "passive"))
      (node (ref "D38") (pin "4") (pinfunction "VCC_4") (pintype "passive"))
      (node (ref "D39") (pin "4") (pinfunction "VCC_4") (pintype "passive"))
      (node (ref "D4") (pin "4") (pinfunction "VCC_4") (pintype "passive"))
      (node (ref "D40") (pin "4") (pinfunction "VCC_4") (pintype "passive"))
      (node (ref "D41") (pin "4") (pinfunction "VCC_4") (pintype "passive"))
      (node (ref "D42") (pin "4") (pinfunction "VCC_4") (pintype "passive"))
      (node (ref "D43") (pin "4") (pinfunction "VCC_4") (pintype "passive"))
      (node (ref "D44") (pin "4") (pinfunction "VCC_4") (pintype "passive"))
      (node (ref "D45") (pin "4") (pinfunction "VCC_4") (pintype "passive"))
      (node (ref "D46") (pin "4") (pinfunction "VCC_4") (pintype "passive"))
      (node (ref "D47") (pin "4") (pinfunction "VCC_4") (pintype "passive"))
      (node (ref "D48") (pin "4") (pinfunction "VCC_4") (pintype "passive"))
      (node (ref "D49") (pin "4") (pinfunction "VCC_4") (pintype "passive"))
      (node (ref "D5") (pin "4") (pinfunction "VCC_4") (pintype "passive"))
      (node (ref "D50") (pin "4") (pinfunction "VCC_4") (pintype "passive"))
      (node (ref "D51") (pin "4") (pinfunction "VCC_4") (pintype "passive"))
      (node (ref "D52") (pin "4") (pinfunction "VCC_4") (pintype "passive"))
      (node (ref "D53") (pin "4") (pinfunction "VCC_4") (pintype "passive"))
      (node (ref "D54") (pin "4") (pinfunction "VCC_4") (pintype "passive"))
      (node (ref "D55") (pin "4") (pinfunction "VCC_4") (pintype "passive"))
      (node (ref "D56") (pin "4") (pinfunction "VCC_4") (pintype "passive"))
      (node (ref "D57") (pin "4") (pinfunction "VCC_4") (pintype "passive"))
      (node (ref "D58") (pin "4") (pinfunction "VCC_4") (pintype "passive"))
      (node (ref "D59") (pin "4") (pinfunction "VCC_4") (pintype "passive"))
      (node (ref "D6") (pin "4") (pinfunction "VCC_4") (pintype "passive"))
      (node (ref "D60") (pin "4") (pinfunction "VCC_4") (pintype "passive"))
      (node (ref "D61") (pin "4") (pinfunction "VCC_4") (pintype "passive"))
      (node (ref "D62") (pin "4") (pinfunction "VCC_4") (pintype "passive"))
      (node (ref "D63") (pin "4") (pinfunction "VCC_4") (pintype "passive"))
      (node (ref "D64") (pin "4") (pinfunction "VCC_4") (pintype "passive"))
      (node (ref "D65") (pin "4") (pinfunction "VCC_4") (pintype "passive"))
      (node (ref "D66") (pin "4") (pinfunction "VCC_4") (pintype "passive"))
      (node (ref "D67") (pin "4") (pinfunction "VCC_4") (pintype "passive"))
      (node (ref "D7") (pin "4") (pinfunction "VCC_4") (pintype "passive"))
      (node (ref "D8") (pin "4") (pinfunction "VCC_4") (pintype "passive"))
      (node (ref "D9") (pin "4") (pinfunction "VCC_4") (pintype "passive"))
      (node (ref "J7") (pin "3") (pinfunction "3_3") (pintype "passive"))
      (node (ref "R1") (pin "2") (pinfunction "2_2") (pintype "passive"))
      (node (ref "R3") (pin "2") (pinfunction "2_2") (pintype "passive"))
      (node (ref "U1") (pin "1") (pinfunction "OUT_1") (pintype "passive"))
      (node (ref "U2") (pin "3") (pinfunction "IN_3") (pintype "passive"))
    )
    (net (code "3") (name "/CKI") (class "Default")
      (node (ref "J1") (pin "26") (pinfunction "P16_26") (pintype "passive"))
      (node (ref "R6") (pin "1") (pinfunction "1_1") (pintype "passive"))
      (node (ref "U4") (pin "2") (pinfunction "S_2") (pintype "passive"))
    )
    (net (code "4") (name "/CKI5V") (class "Default")
      (node (ref "D3") (pin "2") (pinfunction "CKI_2") (pintype "passive"))
      (node (ref "R3") (pin "1") (pinfunction "1_1") (pintype "passive"))
      (node (ref "TP2") (pin "1") (pinfunction "1_1") (pintype "passive"))
      (node (ref "U4") (pin "3") (pinfunction "D_3") (pintype "passive"))
    )
    (net (code "5") (name "/JD_DATA_MCU") (class "Default")
      (node (ref "J1") (pin "18") (pinfunction "P12_18") (pintype "passive"))
    )
    (net (code "6") (name "/P0") (class "Default")
      (node (ref "J1") (pin "2") (pinfunction "P0_2") (pintype "passive"))
      (node (ref "J1") (pin "3") (pinfunction "P0_3") (pintype "passive"))
      (node (ref "J1") (pin "4") (pinfunction "P0_4") (pintype "passive"))
      (node (ref "J1") (pin "5") (pinfunction "P0_5") (pintype "passive"))
      (node (ref "J4") (pin "1") (pinfunction "1_1") (pintype "passive"))
      (node (ref "J4") (pin "2") (pinfunction "2_2") (pintype "passive"))
    )
    (net (code "7") (name "/P1") (class "Default")
      (node (ref "J1") (pin "10") (pinfunction "P1_10") (pintype "passive"))
      (node (ref "J1") (pin "11") (pinfunction "P1_11") (pintype "passive"))
      (node (ref "J1") (pin "12") (pinfunction "P1_12") (pintype "passive"))
      (node (ref "J1") (pin "13") (pinfunction "P1_13") (pintype "passive"))
      (node (ref "J4") (pin "3") (pinfunction "3_3") (pintype "passive"))
      (node (ref "J4") (pin "4") (pinfunction "4_4") (pintype "passive"))
    )
    (net (code "8") (name "/P2") (class "Default")
      (node (ref "J1") (pin "19") (pinfunction "P2_19") (pintype "passive"))
      (node (ref "J1") (pin "20") (pinfunction "P2_20") (pintype "passive"))
      (node (ref "J1") (pin "21") (pinfunction "P2_21") (pintype "passive"))
      (node (ref "J1") (pin "22") (pinfunction "P2_22") (pintype "passive"))
      (node (ref "J4") (pin "5") (pinfunction "5_5") (pintype "passive"))
      (node (ref "J4") (pin "6") (pinfunction "6_6") (pintype "passive"))
    )
    (net (code "9") (name "/P3") (class "Default")
      (node (ref "J1") (pin "1") (pinfunction "P3_1") (pintype "passive"))
      (node (ref "J6") (pin "1") (pinfunction "1_1") (pintype "passive"))
    )
    (net (code "10") (name "/P4") (class "Default")
      (node (ref "J1") (pin "6") (pinfunction "P4_6") (pintype "passive"))
      (node (ref "J6") (pin "3") (pinfunction "3_3") (pintype "passive"))
    )
    (net (code "11") (name "/P6") (class "Default")
      (node (ref "J1") (pin "8") (pinfunction "P6_8") (pintype "passive"))
      (node (ref "J6") (pin "5") (pinfunction "5_5") (pintype "passive"))
    )
    (net (code "12") (name "/P7") (class "Default")
      (node (ref "J1") (pin "9") (pinfunction "P7_9") (pintype "passive"))
      (node (ref "J6") (pin "7") (pinfunction "7_7") (pintype "passive"))
    )
    (net (code "13") (name "/P9") (class "Default")
      (node (ref "J1") (pin "15") (pinfunction "P9_15") (pintype "passive"))
      (node (ref "J6") (pin "9") (pinfunction "9_9") (pintype "passive"))
    )
    (net (code "14") (name "/P13") (class "Default")
      (node (ref "J1") (pin "23") (pinfunction "P13_23") (pintype "passive"))
      (node (ref "J6") (pin "2") (pinfunction "2_2") (pintype "passive"))
    )
    (net (code "15") (name "/P14") (class "Default")
      (node (ref "J1") (pin "24") (pinfunction "P14_24") (pintype "passive"))
      (node (ref "J6") (pin "4") (pinfunction "4_4") (pintype "passive"))
    )
    (net (code "16") (name "/P15") (class "Default")
      (node (ref "J1") (pin "25") (pinfunction "P15_25") (pintype "passive"))
      (node (ref "J6") (pin "6") (pinfunction "6_6") (pintype "passive"))
    )
    (net (code "17") (name "/P19") (class "Default")
      (node (ref "J1") (pin "33") (pinfunction "P19_33") (pintype "passive"))
      (node (ref "J6") (pin "8") (pinfunction "8_8") (pintype "passive"))
    )
    (net (code "18") (name "/P20") (class "Default")
      (node (ref "J1") (pin "34") (pinfunction "P20_34") (pintype "passive"))
      (node (ref "J6") (pin "10") (pinfunction "10_10") (pintype "passive"))
    )
    (net (code "19") (name "/SDI") (class "Default")
      (node (ref "J1") (pin "14") (pinfunction "P8_14") (pintype "passive"))
      (node (ref "R5") (pin "1") (pinfunction "1_1") (pintype "passive"))
      (node (ref "U3") (pin "2") (pinfunction "S_2") (pintype "passive"))
    )
    (net (code "20") (name "/SDI5V") (class "Default")
      (node (ref "D3") (pin "1") (pinfunction "SDI_1") (pintype "passive"))
      (node (ref "R1") (pin "1") (pinfunction "1_1") (pintype "passive"))
      (node (ref "TP1") (pin "1") (pinfunction "1_1") (pintype "passive"))
      (node (ref "U3") (pin "3") (pinfunction "D_3") (pintype "passive"))
    )
    (net (code "21") (name "GND") (class "Default")
      (node (ref "C1") (pin "1") (pinfunction "1_1") (pintype "passive"))
      (node (ref "C2") (pin "1") (pinfunction "1_1") (pintype "passive"))
      (node (ref "C3") (pin "1") (pinfunction "1_1") (pintype "passive"))
      (node (ref "C4") (pin "1") (pinfunction "1_1") (pintype "passive"))
      (node (ref "D10") (pin "3") (pinfunction "GND_3") (pintype "passive"))
      (node (ref "D11") (pin "3") (pinfunction "GND_3") (pintype "passive"))
      (node (ref "D12") (pin "3") (pinfunction "GND_3") (pintype "passive"))
      (node (ref "D13") (pin "3") (pinfunction "GND_3") (pintype "passive"))
      (node (ref "D14") (pin "3") (pinfunction "GND_3") (pintype "passive"))
      (node (ref "D15") (pin "3") (pinfunction "GND_3") (pintype "passive"))
      (node (ref "D16") (pin "3") (pinfunction "GND_3") (pintype "passive"))
      (node (ref "D17") (pin "3") (pinfunction "GND_3") (pintype "passive"))
      (node (ref "D18") (pin "3") (pinfunction "GND_3") (pintype "passive"))
      (node (ref "D19") (pin "3") (pinfunction "GND_3") (pintype "passive"))
      (node (ref "D20") (pin "3") (pinfunction "GND_3") (pintype "passive"))
      (node (ref "D21") (pin "3") (pinfunction "GND_3") (pintype "passive"))
      (node (ref "D22") (pin "3") (pinfunction "GND_3") (pintype "passive"))
      (node (ref "D23") (pin "3") (pinfunction "GND_3") (pintype "passive"))
      (node (ref "D24") (pin "3") (pinfunction "GND_3") (pintype "passive"))
      (node (ref "D25") (pin "3") (pinfunction "GND_3") (pintype "passive"))
      (node (ref "D26") (pin "3") (pinfunction "GND_3") (pintype "passive"))
      (node (ref "D27") (pin "3") (pinfunction "GND_3") (pintype "passive"))
      (node (ref "D28") (pin "3") (pinfunction "GND_3") (pintype "passive"))
      (node (ref "D29") (pin "3") (pinfunction "GND_3") (pintype "passive"))
      (node (ref "D3") (pin "3") (pinfunction "GND_3") (pintype "passive"))
      (node (ref "D30") (pin "3") (pinfunction "GND_3") (pintype "passive"))
      (node (ref "D31") (pin "3") (pinfunction "GND_3") (pintype "passive"))
      (node (ref "D32") (pin "3") (pinfunction "GND_3") (pintype "passive"))
      (node (ref "D33") (pin "3") (pinfunction "GND_3") (pintype "passive"))
      (node (ref "D34") (pin "3") (pinfunction "GND_3") (pintype "passive"))
      (node (ref "D35") (pin "3") (pinfunction "GND_3") (pintype "passive"))
      (node (ref "D36") (pin "3") (pinfunction "GND_3") (pintype "passive"))
      (node (ref "D37") (pin "3") (pinfunction "GND_3") (pintype "passive"))
      (node (ref "D38") (pin "3") (pinfunction "GND_3") (pintype "passive"))
      (node (ref "D39") (pin "3") (pinfunction "GND_3") (pintype "passive"))
      (node (ref "D4") (pin "3") (pinfunction "GND_3") (pintype "passive"))
      (node (ref "D40") (pin "3") (pinfunction "GND_3") (pintype "passive"))
      (node (ref "D41") (pin "3") (pinfunction "GND_3") (pintype "passive"))
      (node (ref "D42") (pin "3") (pinfunction "GND_3") (pintype "passive"))
      (node (ref "D43") (pin "3") (pinfunction "GND_3") (pintype "passive"))
      (node (ref "D44") (pin "3") (pinfunction "GND_3") (pintype "passive"))
      (node (ref "D45") (pin "3") (pinfunction "GND_3") (pintype "passive"))
      (node (ref "D46") (pin "3") (pinfunction "GND_3") (pintype "passive"))
      (node (ref "D47") (pin "3") (pinfunction "GND_3") (pintype "passive"))
      (node (ref "D48") (pin "3") (pinfunction "GND_3") (pintype "passive"))
      (node (ref "D49") (pin "3") (pinfunction "GND_3") (pintype "passive"))
      (node (ref "D5") (pin "3") (pinfunction "GND_3") (pintype "passive"))
      (node (ref "D50") (pin "3") (pinfunction "GND_3") (pintype "passive"))
      (node (ref "D51") (pin "3") (pinfunction "GND_3") (pintype "passive"))
      (node (ref "D52") (pin "3") (pinfunction "GND_3") (pintype "passive"))
      (node (ref "D53") (pin "3") (pinfunction "GND_3") (pintype "passive"))
      (node (ref "D54") (pin "3") (pinfunction "GND_3") (pintype "passive"))
      (node (ref "D55") (pin "3") (pinfunction "GND_3") (pintype "passive"))
      (node (ref "D56") (pin "3") (pinfunction "GND_3") (pintype "passive"))
      (node (ref "D57") (pin "3") (pinfunction "GND_3") (pintype "passive"))
      (node (ref "D58") (pin "3") (pinfunction "GND_3") (pintype "passive"))
      (node (ref "D59") (pin "3") (pinfunction "GND_3") (pintype "passive"))
      (node (ref "D6") (pin "3") (pinfunction "GND_3") (pintype "passive"))
      (node (ref "D60") (pin "3") (pinfunction "GND_3") (pintype "passive"))
      (node (ref "D61") (pin "3") (pinfunction "GND_3") (pintype "passive"))
      (node (ref "D62") (pin "3") (pinfunction "GND_3") (pintype "passive"))
      (node (ref "D63") (pin "3") (pinfunction "GND_3") (pintype "passive"))
      (node (ref "D64") (pin "3") (pinfunction "GND_3") (pintype "passive"))
      (node (ref "D65") (pin "3") (pinfunction "GND_3") (pintype "passive"))
      (node (ref "D66") (pin "3") (pinfunction "GND_3") (pintype "passive"))
      (node (ref "D67") (pin "3") (pinfunction "GND_3") (pintype "passive"))
      (node (ref "D68") (pin "1") (pinfunction "C_1") (pintype "passive"))
      (node (ref "D7") (pin "3") (pinfunction "GND_3") (pintype "passive"))
      (node (ref "D8") (pin "3") (pinfunction "GND_3") (pintype "passive"))
      (node (ref "D9") (pin "3") (pinfunction "GND_3") (pintype "passive"))
      (node (ref "J1") (pin "38") (pinfunction "GND_38") (pintype "passive"))
      (node (ref "J1") (pin "39") (pinfunction "GND_39") (pintype "passive"))
      (node (ref "J1") (pin "40") (pinfunction "GND_40") (pintype "passive"))
      (node (ref "J2") (pin "2") (pinfunction "-_2") (pintype "passive"))
      (node (ref "J2") (pin "4") (pinfunction "-_4") (pintype "passive"))
      (node (ref "J7") (pin "1") (pinfunction "1_1") (pintype "passive"))
      (node (ref "U1") (pin "2") (pinfunction "GND_2") (pintype "passive"))
      (node (ref "U1") (pin "4") (pinfunction "EN_4") (pintype "passive"))
      (node (ref "U2") (pin "1") (pinfunction "ADJ/GND_1") (pintype "passive"))
    )
    (net (code "22") (name "Net-(D2-C)") (class "Default")
      (node (ref "D2") (pin "1") (pinfunction "C_1") (pintype "passive"))
      (node (ref "J1") (pin "27") (pinfunction "3V3_27") (pintype "passive"))
      (node (ref "J1") (pin "28") (pinfunction "3V3_28") (pintype "passive"))
      (node (ref "J1") (pin "29") (pinfunction "3V3_29") (pintype "passive"))
      (node (ref "J1") (pin "30") (pinfunction "3V3_30") (pintype "passive"))
      (node (ref "J1") (pin "31") (pinfunction "3V3_31") (pintype "passive"))
      (node (ref "J1") (pin "32") (pinfunction "3V3_32") (pintype "passive"))
    )
    (net (code "23") (name "Net-(D3-CKO)") (class "Default")
      (node (ref "D3") (pin "5") (pinfunction "CKO_5") (pintype "passive"))
      (node (ref "D4") (pin "2") (pinfunction "CKI_2") (pintype "passive"))
    )
    (net (code "24") (name "Net-(D3-SDO)") (class "Default")
      (node (ref "D3") (pin "6") (pinfunction "SDO_6") (pintype "passive"))
      (node (ref "D4") (pin "1") (pinfunction "SDI_1") (pintype "passive"))
    )
    (net (code "25") (name "Net-(D4-CKO)") (class "Default")
      (node (ref "D4") (pin "5") (pinfunction "CKO_5") (pintype "passive"))
      (node (ref "D5") (pin "2") (pinfunction "CKI_2") (pintype "passive"))
    )
    (net (code "26") (name "Net-(D4-SDO)") (class "Default")
      (node (ref "D4") (pin "6") (pinfunction "SDO_6") (pintype "passive"))
      (node (ref "D5") (pin "1") (pinfunction "SDI_1") (pintype "passive"))
    )
    (net (code "27") (name "Net-(D5-CKO)") (class "Default")
      (node (ref "D5") (pin "5") (pinfunction "CKO_5") (pintype "passive"))
      (node (ref "D6") (pin "2") (pinfunction "CKI_2") (pintype "passive"))
    )
    (net (code "28") (name "Net-(D5-SDO)") (class "Default")
      (node (ref "D5") (pin "6") (pinfunction "SDO_6") (pintype "passive"))
      (node (ref "D6") (pin "1") (pinfunction "SDI_1") (pintype "passive"))
    )
    (net (code "29") (name "Net-(D6-CKO)") (class "Default")
      (node (ref "D6") (pin "5") (pinfunction "CKO_5") (pintype "passive"))
      (node (ref "D7") (pin "2") (pinfunction "CKI_2") (pintype "passive"))
    )
    (net (code "30") (name "Net-(D6-SDO)") (class "Default")
      (node (ref "D6") (pin "6") (pinfunction "SDO_6") (pintype "passive"))
      (node (ref "D7") (pin "1") (pinfunction "SDI_1") (pintype "passive"))
    )
    (net (code "31") (name "Net-(D7-CKO)") (class "Default")
      (node (ref "D7") (pin "5") (pinfunction "CKO_5") (pintype "passive"))
      (node (ref "D8") (pin "2") (pinfunction "CKI_2") (pintype "passive"))
    )
    (net (code "32") (name "Net-(D7-SDO)") (class "Default")
      (node (ref "D7") (pin "6") (pinfunction "SDO_6") (pintype "passive"))
      (node (ref "D8") (pin "1") (pinfunction "SDI_1") (pintype "passive"))
    )
    (net (code "33") (name "Net-(D8-CKO)") (class "Default")
      (node (ref "D8") (pin "5") (pinfunction "CKO_5") (pintype "passive"))
      (node (ref "D9") (pin "2") (pinfunction "CKI_2") (pintype "passive"))
    )
    (net (code "34") (name "Net-(D8-SDO)") (class "Default")
      (node (ref "D8") (pin "6") (pinfunction "SDO_6") (pintype "passive"))
      (node (ref "D9") (pin "1") (pinfunction "SDI_1") (pintype "passive"))
    )
    (net (code "35") (name "Net-(D10-CKI)") (class "Default")
      (node (ref "D10") (pin "2") (pinfunction "CKI_2") (pintype "passive"))
      (node (ref "D9") (pin "5") (pinfunction "CKO_5") (pintype "passive"))
    )
    (net (code "36") (name "Net-(D10-CKO)") (class "Default")
      (node (ref "D10") (pin "5") (pinfunction "CKO_5") (pintype "passive"))
      (node (ref "D11") (pin "2") (pinfunction "CKI_2") (pintype "passive"))
    )
    (net (code "37") (name "Net-(D10-SDI)") (class "Default")
      (node (ref "D10") (pin "1") (pinfunction "SDI_1") (pintype "passive"))
      (node (ref "D9") (pin "6") (pinfunction "SDO_6") (pintype "passive"))
    )
    (net (code "38") (name "Net-(D10-SDO)") (class "Default")
      (node (ref "D10") (pin "6") (pinfunction "SDO_6") (pintype "passive"))
      (node (ref "D11") (pin "1") (pinfunction "SDI_1") (pintype "passive"))
    )
    (net (code "39") (name "Net-(D11-CKO)") (class "Default")
      (node (ref "D11") (pin "5") (pinfunction "CKO_5") (pintype "passive"))
      (node (ref "D12") (pin "2") (pinfunction "CKI_2") (pintype "passive"))
    )
    (net (code "40") (name "Net-(D11-SDO)") (class "Default")
      (node (ref "D11") (pin "6") (pinfunction "SDO_6") (pintype "passive"))
      (node (ref "D12") (pin "1") (pinfunction "SDI_1") (pintype "passive"))
    )
    (net (code "41") (name "Net-(D12-CKO)") (class "Default")
      (node (ref "D12") (pin "5") (pinfunction "CKO_5") (pintype "passive"))
      (node (ref "D13") (pin "2") (pinfunction "CKI_2") (pintype "passive"))
    )
    (net (code "42") (name "Net-(D12-SDO)") (class "Default")
      (node (ref "D12") (pin "6") (pinfunction "SDO_6") (pintype "passive"))
      (node (ref "D13") (pin "1") (pinfunction "SDI_1") (pintype "passive"))
    )
    (net (code "43") (name "Net-(D13-CKO)") (class "Default")
      (node (ref "D13") (pin "5") (pinfunction "CKO_5") (pintype "passive"))
      (node (ref "D14") (pin "2") (pinfunction "CKI_2") (pintype "passive"))
    )
    (net (code "44") (name "Net-(D13-SDO)") (class "Default")
      (node (ref "D13") (pin "6") (pinfunction "SDO_6") (pintype "passive"))
      (node (ref "D14") (pin "1") (pinfunction "SDI_1") (pintype "passive"))
    )
    (net (code "45") (name "Net-(D14-CKO)") (class "Default")
      (node (ref "D14") (pin "5") (pinfunction "CKO_5") (pintype "passive"))
      (node (ref "D15") (pin "2") (pinfunction "CKI_2") (pintype "passive"))
    )
    (net (code "46") (name "Net-(D14-SDO)") (class "Default")
      (node (ref "D14") (pin "6") (pinfunction "SDO_6") (pintype "passive"))
      (node (ref "D15") (pin "1") (pinfunction "SDI_1") (pintype "passive"))
    )
    (net (code "47") (name "Net-(D15-CKO)") (class "Default")
      (node (ref "D15") (pin "5") (pinfunction "CKO_5") (pintype "passive"))
      (node (ref "D16") (pin "2") (pinfunction "CKI_2") (pintype "passive"))
    )
    (net (code "48") (name "Net-(D15-SDO)") (class "Default")
      (node (ref "D15") (pin "6") (pinfunction "SDO_6") (pintype "passive"))
      (node (ref "D16") (pin "1") (pinfunction "SDI_1") (pintype "passive"))
    )
    (net (code "49") (name "Net-(D16-CKO)") (class "Default")
      (node (ref "D16") (pin "5") (pinfunction "CKO_5") (pintype "passive"))
      (node (ref "D17") (pin "2") (pinfunction "CKI_2") (pintype "passive"))
    )
    (net (code "50") (name "Net-(D16-SDO)") (class "Default")
      (node (ref "D16") (pin "6") (pinfunction "SDO_6") (pintype "passive"))
      (node (ref "D17") (pin "1") (pinfunction "SDI_1") (pintype "passive"))
    )
    (net (code "51") (name "Net-(D17-CKO)") (class "Default")
      (node (ref "D17") (pin "5") (pinfunction "CKO_5") (pintype "passive"))
      (node (ref "D32") (pin "2") (pinfunction "CKI_2") (pintype "passive"))
    )
    (net (code "52") (name "Net-(D17-SDO)") (class "Default")
      (node (ref "D17") (pin "6") (pinfunction "SDO_6") (pintype "passive"))
      (node (ref "D32") (pin "1") (pinfunction "SDI_1") (pintype "passive"))
    )
    (net (code "53") (name "Net-(D18-CKI)") (class "Default")
      (node (ref "D18") (pin "2") (pinfunction "CKI_2") (pintype "passive"))
      (node (ref "D19") (pin "5") (pinfunction "CKO_5") (pintype "passive"))
    )
    (net (code "54") (name "Net-(D18-CKO)") (class "Default")
      (node (ref "D18") (pin "5") (pinfunction "CKO_5") (pintype "passive"))
      (node (ref "D33") (pin "2") (pinfunction "CKI_2") (pintype "passive"))
    )
    (net (code "55") (name "Net-(D18-SDI)") (class "Default")
      (node (ref "D18") (pin "1") (pinfunction "SDI_1") (pintype "passive"))
      (node (ref "D19") (pin "6") (pinfunction "SDO_6") (pintype "passive"))
    )
    (net (code "56") (name "Net-(D18-SDO)") (class "Default")
      (node (ref "D18") (pin "6") (pinfunction "SDO_6") (pintype "passive"))
      (node (ref "D33") (pin "1") (pinfunction "SDI_1") (pintype "passive"))
    )
    (net (code "57") (name "Net-(D19-CKI)") (class "Default")
      (node (ref "D19") (pin "2") (pinfunction "CKI_2") (pintype "passive"))
      (node (ref "D20") (pin "5") (pinfunction "CKO_5") (pintype "passive"))
    )
    (net (code "58") (name "Net-(D19-SDI)") (class "Default")
      (node (ref "D19") (pin "1") (pinfunction "SDI_1") (pintype "passive"))
      (node (ref "D20") (pin "6") (pinfunction "SDO_6") (pintype "passive"))
    )
    (net (code "59") (name "Net-(D20-CKI)") (class "Default")
      (node (ref "D20") (pin "2") (pinfunction "CKI_2") (pintype "passive"))
      (node (ref "D21") (pin "5") (pinfunction "CKO_5") (pintype "passive"))
    )
    (net (code "60") (name "Net-(D20-SDI)") (class "Default")
      (node (ref "D20") (pin "1") (pinfunction "SDI_1") (pintype "passive"))
      (node (ref "D21") (pin "6") (pinfunction "SDO_6") (pintype "passive"))
    )
    (net (code "61") (name "Net-(D21-CKI)") (class "Default")
      (node (ref "D21") (pin "2") (pinfunction "CKI_2") (pintype "passive"))
      (node (ref "D22") (pin "5") (pinfunction "CKO_5") (pintype "passive"))
    )
    (net (code "62") (name "Net-(D21-SDI)") (class "Default")
      (node (ref "D21") (pin "1") (pinfunction "SDI_1") (pintype "passive"))
      (node (ref "D22") (pin "6") (pinfunction "SDO_6") (pintype "passive"))
    )
    (net (code "63") (name "Net-(D22-CKI)") (class "Default")
      (node (ref "D22") (pin "2") (pinfunction "CKI_2") (pintype "passive"))
      (node (ref "D23") (pin "5") (pinfunction "CKO_5") (pintype "passive"))
    )
    (net (code "64") (name "Net-(D22-SDI)") (class "Default")
      (node (ref "D22") (pin "1") (pinfunction "SDI_1") (pintype "passive"))
      (node (ref "D23") (pin "6") (pinfunction "SDO_6") (pintype "passive"))
    )
    (net (code "65") (name "Net-(D23-CKI)") (class "Default")
      (node (ref "D23") (pin "2") (pinfunction "CKI_2") (pintype "passive"))
      (node (ref "D24") (pin "5") (pinfunction "CKO_5") (pintype "passive"))
    )
    (net (code "66") (name "Net-(D23-SDI)") (class "Default")
      (node (ref "D23") (pin "1") (pinfunction "SDI_1") (pintype "passive"))
      (node (ref "D24") (pin "6") (pinfunction "SDO_6") (pintype "passive"))
    )
    (net (code "67") (name "Net-(D24-CKI)") (class "Default")
      (node (ref "D24") (pin "2") (pinfunction "CKI_2") (pintype "passive"))
      (node (ref "D25") (pin "5") (pinfunction "CKO_5") (pintype "passive"))
    )
    (net (code "68") (name "Net-(D24-SDI)") (class "Default")
      (node (ref "D24") (pin "1") (pinfunction "SDI_1") (pintype "passive"))
      (node (ref "D25") (pin "6") (pinfunction "SDO_6") (pintype "passive"))
    )
    (net (code "69") (name "Net-(D25-CKI)") (class "Default")
      (node (ref "D25") (pin "2") (pinfunction "CKI_2") (pintype "passive"))
      (node (ref "D26") (pin "5") (pinfunction "CKO_5") (pintype "passive"))
    )
    (net (code "70") (name "Net-(D25-SDI)") (class "Default")
      (node (ref "D25") (pin "1") (pinfunction "SDI_1") (pintype "passive"))
      (node (ref "D26") (pin "6") (pinfunction "SDO_6") (pintype "passive"))
    )
    (net (code "71") (name "Net-(D26-CKI)") (class "Default")
      (node (ref "D26") (pin "2") (pinfunction "CKI_2") (pintype "passive"))
      (node (ref "D27") (pin "5") (pinfunction "CKO_5") (pintype "passive"))
    )
    (net (code "72") (name "Net-(D26-SDI)") (class "Default")
      (node (ref "D26") (pin "1") (pinfunction "SDI_1") (pintype "passive"))
      (node (ref "D27") (pin "6") (pinfunction "SDO_6") (pintype "passive"))
    )
    (net (code "73") (name "Net-(D27-CKI)") (class "Default")
      (node (ref "D27") (pin "2") (pinfunction "CKI_2") (pintype "passive"))
      (node (ref "D28") (pin "5") (pinfunction "CKO_5") (pintype "passive"))
    )
    (net (code "74") (name "Net-(D27-SDI)") (class "Default")
      (node (ref "D27") (pin "1") (pinfunction "SDI_1") (pintype "passive"))
      (node (ref "D28") (pin "6") (pinfunction "SDO_6") (pintype "passive"))
    )
    (net (code "75") (name "Net-(D28-CKI)") (class "Default")
      (node (ref "D28") (pin "2") (pinfunction "CKI_2") (pintype "passive"))
      (node (ref "D29") (pin "5") (pinfunction "CKO_5") (pintype "passive"))
    )
    (net (code "76") (name "Net-(D28-SDI)") (class "Default")
      (node (ref "D28") (pin "1") (pinfunction "SDI_1") (pintype "passive"))
      (node (ref "D29") (pin "6") (pinfunction "SDO_6") (pintype "passive"))
    )
    (net (code "77") (name "Net-(D29-CKI)") (class "Default")
      (node (ref "D29") (pin "2") (pinfunction "CKI_2") (pintype "passive"))
      (node (ref "D30") (pin "5") (pinfunction "CKO_5") (pintype "passive"))
    )
    (net (code "78") (name "Net-(D29-SDI)") (class "Default")
      (node (ref "D29") (pin "1") (pinfunction "SDI_1") (pintype "passive"))
      (node (ref "D30") (pin "6") (pinfunction "SDO_6") (pintype "passive"))
    )
    (net (code "79") (name "Net-(D30-CKI)") (class "Default")
      (node (ref "D30") (pin "2") (pinfunction "CKI_2") (pintype "passive"))
      (node (ref "D31") (pin "5") (pinfunction "CKO_5") (pintype "passive"))
    )
    (net (code "80") (name "Net-(D30-SDI)") (class "Default")
      (node (ref "D30") (pin "1") (pinfunction "SDI_1") (pintype "passive"))
      (node (ref "D31") (pin "6") (pinfunction "SDO_6") (pintype "passive"))
    )
    (net (code "81") (name "Net-(D31-CKI)") (class "Default")
      (node (ref "D31") (pin "2") (pinfunction "CKI_2") (pintype "passive"))
      (node (ref "D32") (pin "5") (pinfunction "CKO_5") (pintype "passive"))
    )
    (net (code "82") (name "Net-(D31-SDI)") (class "Default")
      (node (ref "D31") (pin "1") (pinfunction "SDI_1") (pintype "passive"))
      (node (ref "D32") (pin "6") (pinfunction "SDO_6") (pintype "passive"))
    )
    (net (code "83") (name "Net-(D33-CKO)") (class "Default")
      (node (ref "D33") (pin "5") (pinfunction "CKO_5") (pintype "passive"))
      (node (ref "D34") (pin "2") (pinfunction "CKI_2") (pintype "passive"))
    )
    (net (code "84") (name "Net-(D33-SDO)") (class "Default")
      (node (ref "D33") (pin "6") (pinfunction "SDO_6") (pintype "passive"))
      (node (ref "D34") (pin "1") (pinfunction "SDI_1") (pintype "passive"))
    )
    (net (code "85") (name "Net-(D34-CKO)") (class "Default")
      (node (ref "D34") (pin "5") (pinfunction "CKO_5") (pintype "passive"))
      (node (ref "D35") (pin "2") (pinfunction "CKI_2") (pintype "passive"))
    )
    (net (code "86") (name "Net-(D34-SDO)") (class "Default")
      (node (ref "D34") (pin "6") (pinfunction "SDO_6") (pintype "passive"))
      (node (ref "D35") (pin "1") (pinfunction "SDI_1") (pintype "passive"))
    )
    (net (code "87") (name "Net-(D35-CKO)") (class "Default")
      (node (ref "D35") (pin "5") (pinfunction "CKO_5") (pintype "passive"))
      (node (ref "D36") (pin "2") (pinfunction "CKI_2") (pintype "passive"))
    )
    (net (code "88") (name "Net-(D35-SDO)") (class "Default")
      (node (ref "D35") (pin "6") (pinfunction "SDO_6") (pintype "passive"))
      (node (ref "D36") (pin "1") (pinfunction "SDI_1") (pintype "passive"))
    )
    (net (code "89") (name "Net-(D36-CKO)") (class "Default")
      (node (ref "D36") (pin "5") (pinfunction "CKO_5") (pintype "passive"))
      (node (ref "D37") (pin "2") (pinfunction "CKI_2") (pintype "passive"))
    )
    (net (code "90") (name "Net-(D36-SDO)") (class "Default")
      (node (ref "D36") (pin "6") (pinfunction "SDO_6") (pintype "passive"))
      (node (ref "D37") (pin "1") (pinfunction "SDI_1") (pintype "passive"))
    )
    (net (code "91") (name "Net-(D37-CKO)") (class "Default")
      (node (ref "D37") (pin "5") (pinfunction "CKO_5") (pintype "passive"))
      (node (ref "D38") (pin "2") (pinfunction "CKI_2") (pintype "passive"))
    )
    (net (code "92") (name "Net-(D37-SDO)") (class "Default")
      (node (ref "D37") (pin "6") (pinfunction "SDO_6") (pintype "passive"))
      (node (ref "D38") (pin "1") (pinfunction "SDI_1") (pintype "passive"))
    )
    (net (code "93") (name "Net-(D38-CKO)") (class "Default")
      (node (ref "D38") (pin "5") (pinfunction "CKO_5") (pintype "passive"))
      (node (ref "D39") (pin "2") (pinfunction "CKI_2") (pintype "passive"))
    )
    (net (code "94") (name "Net-(D38-SDO)") (class "Default")
      (node (ref "D38") (pin "6") (pinfunction "SDO_6") (pintype "passive"))
      (node (ref "D39") (pin "1") (pinfunction "SDI_1") (pintype "passive"))
    )
    (net (code "95") (name "Net-(D39-CKO)") (class "Default")
      (node (ref "D39") (pin "5") (pinfunction "CKO_5") (pintype "passive"))
      (node (ref "D40") (pin "2") (pinfunction "CKI_2") (pintype "passive"))
    )
    (net (code "96") (name "Net-(D39-SDO)") (class "Default")
      (node (ref "D39") (pin "6") (pinfunction "SDO_6") (pintype "passive"))
      (node (ref "D40") (pin "1") (pinfunction "SDI_1") (pintype "passive"))
    )
    (net (code "97") (name "Net-(D40-CKO)") (class "Default")
      (node (ref "D40") (pin "5") (pinfunction "CKO_5") (pintype "passive"))
      (node (ref "D41") (pin "2") (pinfunction "CKI_2") (pintype "passive"))
    )
    (net (code "98") (name "Net-(D40-SDO)") (class "Default")
      (node (ref "D40") (pin "6") (pinfunction "SDO_6") (pintype "passive"))
      (node (ref "D41") (pin "1") (pinfunction "SDI_1") (pintype "passive"))
    )
    (net (code "99") (name "Net-(D41-CKO)") (class "Default")
      (node (ref "D41") (pin "5") (pinfunction "CKO_5") (pintype "passive"))
      (node (ref "D42") (pin "2") (pinfunction "CKI_2") (pintype "passive"))
    )
    (net (code "100") (name "Net-(D41-SDO)") (class "Default")
      (node (ref "D41") (pin "6") (pinfunction "SDO_6") (pintype "passive"))
      (node (ref "D42") (pin "1") (pinfunction "SDI_1") (pintype "passive"))
    )
    (net (code "101") (name "Net-(D42-CKO)") (class "Default")
      (node (ref "D42") (pin "5") (pinfunction "CKO_5") (pintype "passive"))
      (node (ref "D43") (pin "2") (pinfunction "CKI_2") (pintype "passive"))
    )
    (net (code "102") (name "Net-(D42-SDO)") (class "Default")
      (node (ref "D42") (pin "6") (pinfunction "SDO_6") (pintype "passive"))
      (node (ref "D43") (pin "1") (pinfunction "SDI_1") (pintype "passive"))
    )
    (net (code "103") (name "Net-(D43-CKO)") (class "Default")
      (node (ref "D43") (pin "5") (pinfunction "CKO_5") (pintype "passive"))
      (node (ref "D44") (pin "2") (pinfunction "CKI_2") (pintype "passive"))
    )
    (net (code "104") (name "Net-(D43-SDO)") (class "Default")
      (node (ref "D43") (pin "6") (pinfunction "SDO_6") (pintype "passive"))
      (node (ref "D44") (pin "1") (pinfunction "SDI_1") (pintype "passive"))
    )
    (net (code "105") (name "Net-(D44-CKO)") (class "Default")
      (node (ref "D44") (pin "5") (pinfunction "CKO_5") (pintype "passive"))
      (node (ref "D45") (pin "2") (pinfunction "CKI_2") (pintype "passive"))
    )
    (net (code "106") (name "Net-(D44-SDO)") (class "Default")
      (node (ref "D44") (pin "6") (pinfunction "SDO_6") (pintype "passive"))
      (node (ref "D45") (pin "1") (pinfunction "SDI_1") (pintype "passive"))
    )
    (net (code "107") (name "Net-(D45-CKO)") (class "Default")
      (node (ref "D45") (pin "5") (pinfunction "CKO_5") (pintype "passive"))
      (node (ref "D46") (pin "2") (pinfunction "CKI_2") (pintype "passive"))
    )
    (net (code "108") (name "Net-(D45-SDO)") (class "Default")
      (node (ref "D45") (pin "6") (pinfunction "SDO_6") (pintype "passive"))
      (node (ref "D46") (pin "1") (pinfunction "SDI_1") (pintype "passive"))
    )
    (net (code "109") (name "Net-(D46-CKO)") (class "Default")
      (node (ref "D46") (pin "5") (pinfunction "CKO_5") (pintype "passive"))
      (node (ref "D47") (pin "2") (pinfunction "CKI_2") (pintype "passive"))
    )
    (net (code "110") (name "Net-(D46-SDO)") (class "Default")
      (node (ref "D46") (pin "6") (pinfunction "SDO_6") (pintype "passive"))
      (node (ref "D47") (pin "1") (pinfunction "SDI_1") (pintype "passive"))
    )
    (net (code "111") (name "Net-(D47-CKO)") (class "Default")
      (node (ref "D47") (pin "5") (pinfunction "CKO_5") (pintype "passive"))
      (node (ref "D62") (pin "2") (pinfunction "CKI_2") (pintype "passive"))
    )
    (net (code "112") (name "Net-(D47-SDO)") (class "Default")
      (node (ref "D47") (pin "6") (pinfunction "SDO_6") (pintype "passive"))
      (node (ref "D62") (pin "1") (pinfunction "SDI_1") (pintype "passive"))
    )
    (net (code "113") (name "Net-(D48-CKI)") (class "Default")
      (node (ref "D48") (pin "2") (pinfunction "CKI_2") (pintype "passive"))
      (node (ref "D49") (pin "5") (pinfunction "CKO_5") (pintype "passive"))
    )
    (net (code "114") (name "Net-(D48-CKO)") (class "Default")
      (node (ref "D48") (pin "5") (pinfunction "CKO_5") (pintype "passive"))
      (node (ref "D63") (pin "2") (pinfunction "CKI_2") (pintype "passive"))
    )
    (net (code "115") (name "Net-(D48-SDI)") (class "Default")
      (node (ref "D48") (pin "1") (pinfunction "SDI_1") (pintype "passive"))
      (node (ref "D49") (pin "6") (pinfunction "SDO_6") (pintype "passive"))
    )
    (net (code "116") (name "Net-(D48-SDO)") (class "Default")
      (node (ref "D48") (pin "6") (pinfunction "SDO_6") (pintype "passive"))
      (node (ref "D63") (pin "1") (pinfunction "SDI_1") (pintype "passive"))
    )
    (net (code "117") (name "Net-(D49-CKI)") (class "Default")
      (node (ref "D49") (pin "2") (pinfunction "CKI_2") (pintype "passive"))
      (node (ref "D50") (pin "5") (pinfunction "CKO_5") (pintype "passive"))
    )
    (net (code "118") (name "Net-(D49-SDI)") (class "Default")
      (node (ref "D49") (pin "1") (pinfunction "SDI_1") (pintype "passive"))
      (node (ref "D50") (pin "6") (pinfunction "SDO_6") (pintype "passive"))
    )
    (net (code "119") (name "Net-(D50-CKI)") (class "Default")
      (node (ref "D50") (pin "2") (pinfunction "CKI_2") (pintype "passive"))
      (node (ref "D51") (pin "5") (pinfunction "CKO_5") (pintype "passive"))
    )
    (net (code "120") (name "Net-(D50-SDI)") (class "Default")
      (node (ref "D50") (pin "1") (pinfunction "SDI_1") (pintype "passive"))
      (node (ref "D51") (pin "6") (pinfunction "SDO_6") (pintype "passive"))
    )
    (net (code "121") (name "Net-(D51-CKI)") (class "Default")
      (node (ref "D51") (pin "2") (pinfunction "CKI_2") (pintype "passive"))
      (node (ref "D52") (pin "5") (pinfunction "CKO_5") (pintype "passive"))
    )
    (net (code "122") (name "Net-(D51-SDI)") (class "Default")
      (node (ref "D51") (pin "1") (pinfunction "SDI_1") (pintype "passive"))
      (node (ref "D52") (pin "6") (pinfunction "SDO_6") (pintype "passive"))
    )
    (net (code "123") (name "Net-(D52-CKI)") (class "Default")
      (node (ref "D52") (pin "2") (pinfunction "CKI_2") (pintype "passive"))
      (node (ref "D53") (pin "5") (pinfunction "CKO_5") (pintype "passive"))
    )
    (net (code "124") (name "Net-(D52-SDI)") (class "Default")
      (node (ref "D52") (pin "1") (pinfunction "SDI_1") (pintype "passive"))
      (node (ref "D53") (pin "6") (pinfunction "SDO_6") (pintype "passive"))
    )
    (net (code "125") (name "Net-(D53-CKI)") (class "Default")
      (node (ref "D53") (pin "2") (pinfunction "CKI_2") (pintype "passive"))
      (node (ref "D54") (pin "5") (pinfunction "CKO_5") (pintype "passive"))
    )
    (net (code "126") (name "Net-(D53-SDI)") (class "Default")
      (node (ref "D53") (pin "1") (pinfunction "SDI_1") (pintype "passive"))
      (node (ref "D54") (pin "6") (pinfunction "SDO_6") (pintype "passive"))
    )
    (net (code "127") (name "Net-(D54-CKI)") (class "Default")
      (node (ref "D54") (pin "2") (pinfunction "CKI_2") (pintype "passive"))
      (node (ref "D55") (pin "5") (pinfunction "CKO_5") (pintype "passive"))
    )
    (net (code "128") (name "Net-(D54-SDI)") (class "Default")
      (node (ref "D54") (pin "1") (pinfunction "SDI_1") (pintype "passive"))
      (node (ref "D55") (pin "6") (pinfunction "SDO_6") (pintype "passive"))
    )
    (net (code "129") (name "Net-(D55-CKI)") (class "Default")
      (node (ref "D55") (pin "2") (pinfunction "CKI_2") (pintype "passive"))
      (node (ref "D56") (pin "5") (pinfunction "CKO_5") (pintype "passive"))
    )
    (net (code "130") (name "Net-(D55-SDI)") (class "Default")
      (node (ref "D55") (pin "1") (pinfunction "SDI_1") (pintype "passive"))
      (node (ref "D56") (pin "6") (pinfunction "SDO_6") (pintype "passive"))
    )
    (net (code "131") (name "Net-(D56-CKI)") (class "Default")
      (node (ref "D56") (pin "2") (pinfunction "CKI_2") (pintype "passive"))
      (node (ref "D57") (pin "5") (pinfunction "CKO_5") (pintype "passive"))
    )
    (net (code "132") (name "Net-(D56-SDI)") (class "Default")
      (node (ref "D56") (pin "1") (pinfunction "SDI_1") (pintype "passive"))
      (node (ref "D57") (pin "6") (pinfunction "SDO_6") (pintype "passive"))
    )
    (net (code "133") (name "Net-(D57-CKI)") (class "Default")
      (node (ref "D57") (pin "2") (pinfunction "CKI_2") (pintype "passive"))
      (node (ref "D58") (pin "5") (pinfunction "CKO_5") (pintype "passive"))
    )
    (net (code "134") (name "Net-(D57-SDI)") (class "Default")
      (node (ref "D57") (pin "1") (pinfunction "SDI_1") (pintype "passive"))
      (node (ref "D58") (pin "6") (pinfunction "SDO_6") (pintype "passive"))
    )
    (net (code "135") (name "Net-(D58-CKI)") (class "Default")
      (node (ref "D58") (pin "2") (pinfunction "CKI_2") (pintype "passive"))
      (node (ref "D59") (pin "5") (pinfunction "CKO_5") (pintype "passive"))
    )
    (net (code "136") (name "Net-(D58-SDI)") (class "Default")
      (node (ref "D58") (pin "1") (pinfunction "SDI_1") (pintype "passive"))
      (node (ref "D59") (pin "6") (pinfunction "SDO_6") (pintype "passive"))
    )
    (net (code "137") (name "Net-(D59-CKI)") (class "Default")
      (node (ref "D59") (pin "2") (pinfunction "CKI_2") (pintype "passive"))
      (node (ref "D60") (pin "5") (pinfunction "CKO_5") (pintype "passive"))
    )
    (net (code "138") (name "Net-(D59-SDI)") (class "Default")
      (node (ref "D59") (pin "1") (pinfunction "SDI_1") (pintype "passive"))
      (node (ref "D60") (pin "6") (pinfunction "SDO_6") (pintype "passive"))
    )
    (net (code "139") (name "Net-(D60-CKI)") (class "Default")
      (node (ref "D60") (pin "2") (pinfunction "CKI_2") (pintype "passive"))
      (node (ref "D61") (pin "5") (pinfunction "CKO_5") (pintype "passive"))
    )
    (net (code "140") (name "Net-(D60-SDI)") (class "Default")
      (node (ref "D60") (pin "1") (pinfunction "SDI_1") (pintype "passive"))
      (node (ref "D61") (pin "6") (pinfunction "SDO_6") (pintype "passive"))
    )
    (net (code "141") (name "Net-(D61-CKI)") (class "Default")
      (node (ref "D61") (pin "2") (pinfunction "CKI_2") (pintype "passive"))
      (node (ref "D62") (pin "5") (pinfunction "CKO_5") (pintype "passive"))
    )
    (net (code "142") (name "Net-(D61-SDI)") (class "Default")
      (node (ref "D61") (pin "1") (pinfunction "SDI_1") (pintype "passive"))
      (node (ref "D62") (pin "6") (pinfunction "SDO_6") (pintype "passive"))
    )
    (net (code "143") (name "Net-(D63-CKO)") (class "Default")
      (node (ref "D63") (pin "5") (pinfunction "CKO_5") (pintype "passive"))
      (node (ref "D64") (pin "2") (pinfunction "CKI_2") (pintype "passive"))
    )
    (net (code "144") (name "Net-(D63-SDO)") (class "Default")
      (node (ref "D63") (pin "6") (pinfunction "SDO_6") (pintype "passive"))
      (node (ref "D64") (pin "1") (pinfunction "SDI_1") (pintype "passive"))
    )
    (net (code "145") (name "Net-(D64-CKO)") (class "Default")
      (node (ref "D64") (pin "5") (pinfunction "CKO_5") (pintype "passive"))
      (node (ref "D65") (pin "2") (pinfunction "CKI_2") (pintype "passive"))
    )
    (net (code "146") (name "Net-(D64-SDO)") (class "Default")
      (node (ref "D64") (pin "6") (pinfunction "SDO_6") (pintype "passive"))
      (node (ref "D65") (pin "1") (pinfunction "SDI_1") (pintype "passive"))
    )
    (net (code "147") (name "Net-(D65-CKO)") (class "Default")
      (node (ref "D65") (pin "5") (pinfunction "CKO_5") (pintype "passive"))
      (node (ref "D66") (pin "2") (pinfunction "CKI_2") (pintype "passive"))
    )
    (net (code "148") (name "Net-(D65-SDO)") (class "Default")
      (node (ref "D65") (pin "6") (pinfunction "SDO_6") (pintype "passive"))
      (node (ref "D66") (pin "1") (pinfunction "SDI_1") (pintype "passive"))
    )
    (net (code "149") (name "Net-(D66-CKO)") (class "Default")
      (node (ref "D66") (pin "5") (pinfunction "CKO_5") (pintype "passive"))
      (node (ref "D67") (pin "2") (pinfunction "CKI_2") (pintype "passive"))
    )
    (net (code "150") (name "Net-(D66-SDO)") (class "Default")
      (node (ref "D66") (pin "6") (pinfunction "SDO_6") (pintype "passive"))
      (node (ref "D67") (pin "1") (pinfunction "SDI_1") (pintype "passive"))
    )
    (net (code "151") (name "Net-(D68-A)") (class "Default")
      (node (ref "D68") (pin "2") (pinfunction "A_2") (pintype "passive"))
      (node (ref "R7") (pin "2") (pinfunction "2_2") (pintype "passive"))
    )
    (net (code "152") (name "Net-(J3-D+)") (class "Default")
      (node (ref "J3") (pin "3") (pinfunction "D+_3") (pintype "passive"))
      (node (ref "R2") (pin "2") (pinfunction "2_2") (pintype "passive"))
    )
    (net (code "153") (name "Net-(J3-D-)") (class "Default")
      (node (ref "J3") (pin "2") (pinfunction "D-_2") (pintype "passive"))
      (node (ref "R2") (pin "1") (pinfunction "1_1") (pintype "passive"))
    )
    (net (code "154") (name "SHIELD") (class "Default")
      (node (ref "C5") (pin "1") (pinfunction "1_1") (pintype "passive"))
      (node (ref "J3") (pin "6") (pinfunction "SHLD1_6") (pintype "passive"))
      (node (ref "J3") (pin "7") (pinfunction "SHLD2_7") (pintype "passive"))
      (node (ref "R4") (pin "1") (pinfunction "1_1") (pintype "passive"))
    )
    (net (code "155") (name "UBIT_GND") (class "Default")
      (node (ref "C5") (pin "2") (pinfunction "2_2") (pintype "passive"))
      (node (ref "J1") (pin "35") (pinfunction "GND_35") (pintype "passive"))
      (node (ref "J1") (pin "36") (pinfunction "GND_36") (pintype "passive"))
      (node (ref "J1") (pin "37") (pinfunction "GND_37") (pintype "passive"))
      (node (ref "J3") (pin "5") (pinfunction "GND_5") (pintype "passive"))
      (node (ref "R4") (pin "2") (pinfunction "2_2") (pintype "passive"))
    )
    (net (code "156") (name "VBUS") (class "Default")
      (node (ref "C1") (pin "2") (pinfunction "2_2") (pintype "passive"))
      (node (ref "J3") (pin "1") (pinfunction "VBUS_1") (pintype "passive"))
      (node (ref "U1") (pin "5") (pinfunction "IN_5") (pintype "passive"))
    )
    (net (code "157") (name "unconnected-(D1-Pad1)") (class "Default")
      (node (ref "D1") (pin "1") (pinfunction "1_1") (pintype "passive+no_connect"))
    )
    (net (code "158") (name "unconnected-(D1-Pad3)") (class "Default")
      (node (ref "D1") (pin "3") (pinfunction "3_3") (pintype "passive+no_connect"))
    )
    (net (code "159") (name "unconnected-(D67-CKO-Pad5)") (class "Default")
      (node (ref "D67") (pin "5") (pinfunction "CKO_5") (pintype "passive+no_connect"))
    )
    (net (code "160") (name "unconnected-(D67-SDO-Pad6)") (class "Default")
      (node (ref "D67") (pin "6") (pinfunction "SDO_6") (pintype "passive+no_connect"))
    )
    (net (code "161") (name "unconnected-(J1-P5-Pad7)") (class "Default")
      (node (ref "J1") (pin "7") (pinfunction "P5_7") (pintype "passive+no_connect"))
    )
    (net (code "162") (name "unconnected-(J1-P10-Pad16)") (class "Default")
      (node (ref "J1") (pin "16") (pinfunction "P10_16") (pintype "passive+no_connect"))
    )
    (net (code "163") (name "unconnected-(J1-P11-Pad17)") (class "Default")
      (node (ref "J1") (pin "17") (pinfunction "P11_17") (pintype "passive+no_connect"))
    )
    (net (code "164") (name "unconnected-(J3-ID-Pad4)") (class "Default")
      (node (ref "J3") (pin "4") (pinfunction "ID_4") (pintype "passive+no_connect"))
    )
    (net (code "165") (name "unconnected-(U1-~{FLAG}-Pad3)") (class "Default")
      (node (ref "U1") (pin "3") (pinfunction "~{FLAG}_3") (pintype "passive+no_connect"))
    )
  )
)
